# RaspFPGA.net
KiCad netlist of a schematic drawn in EAGLE
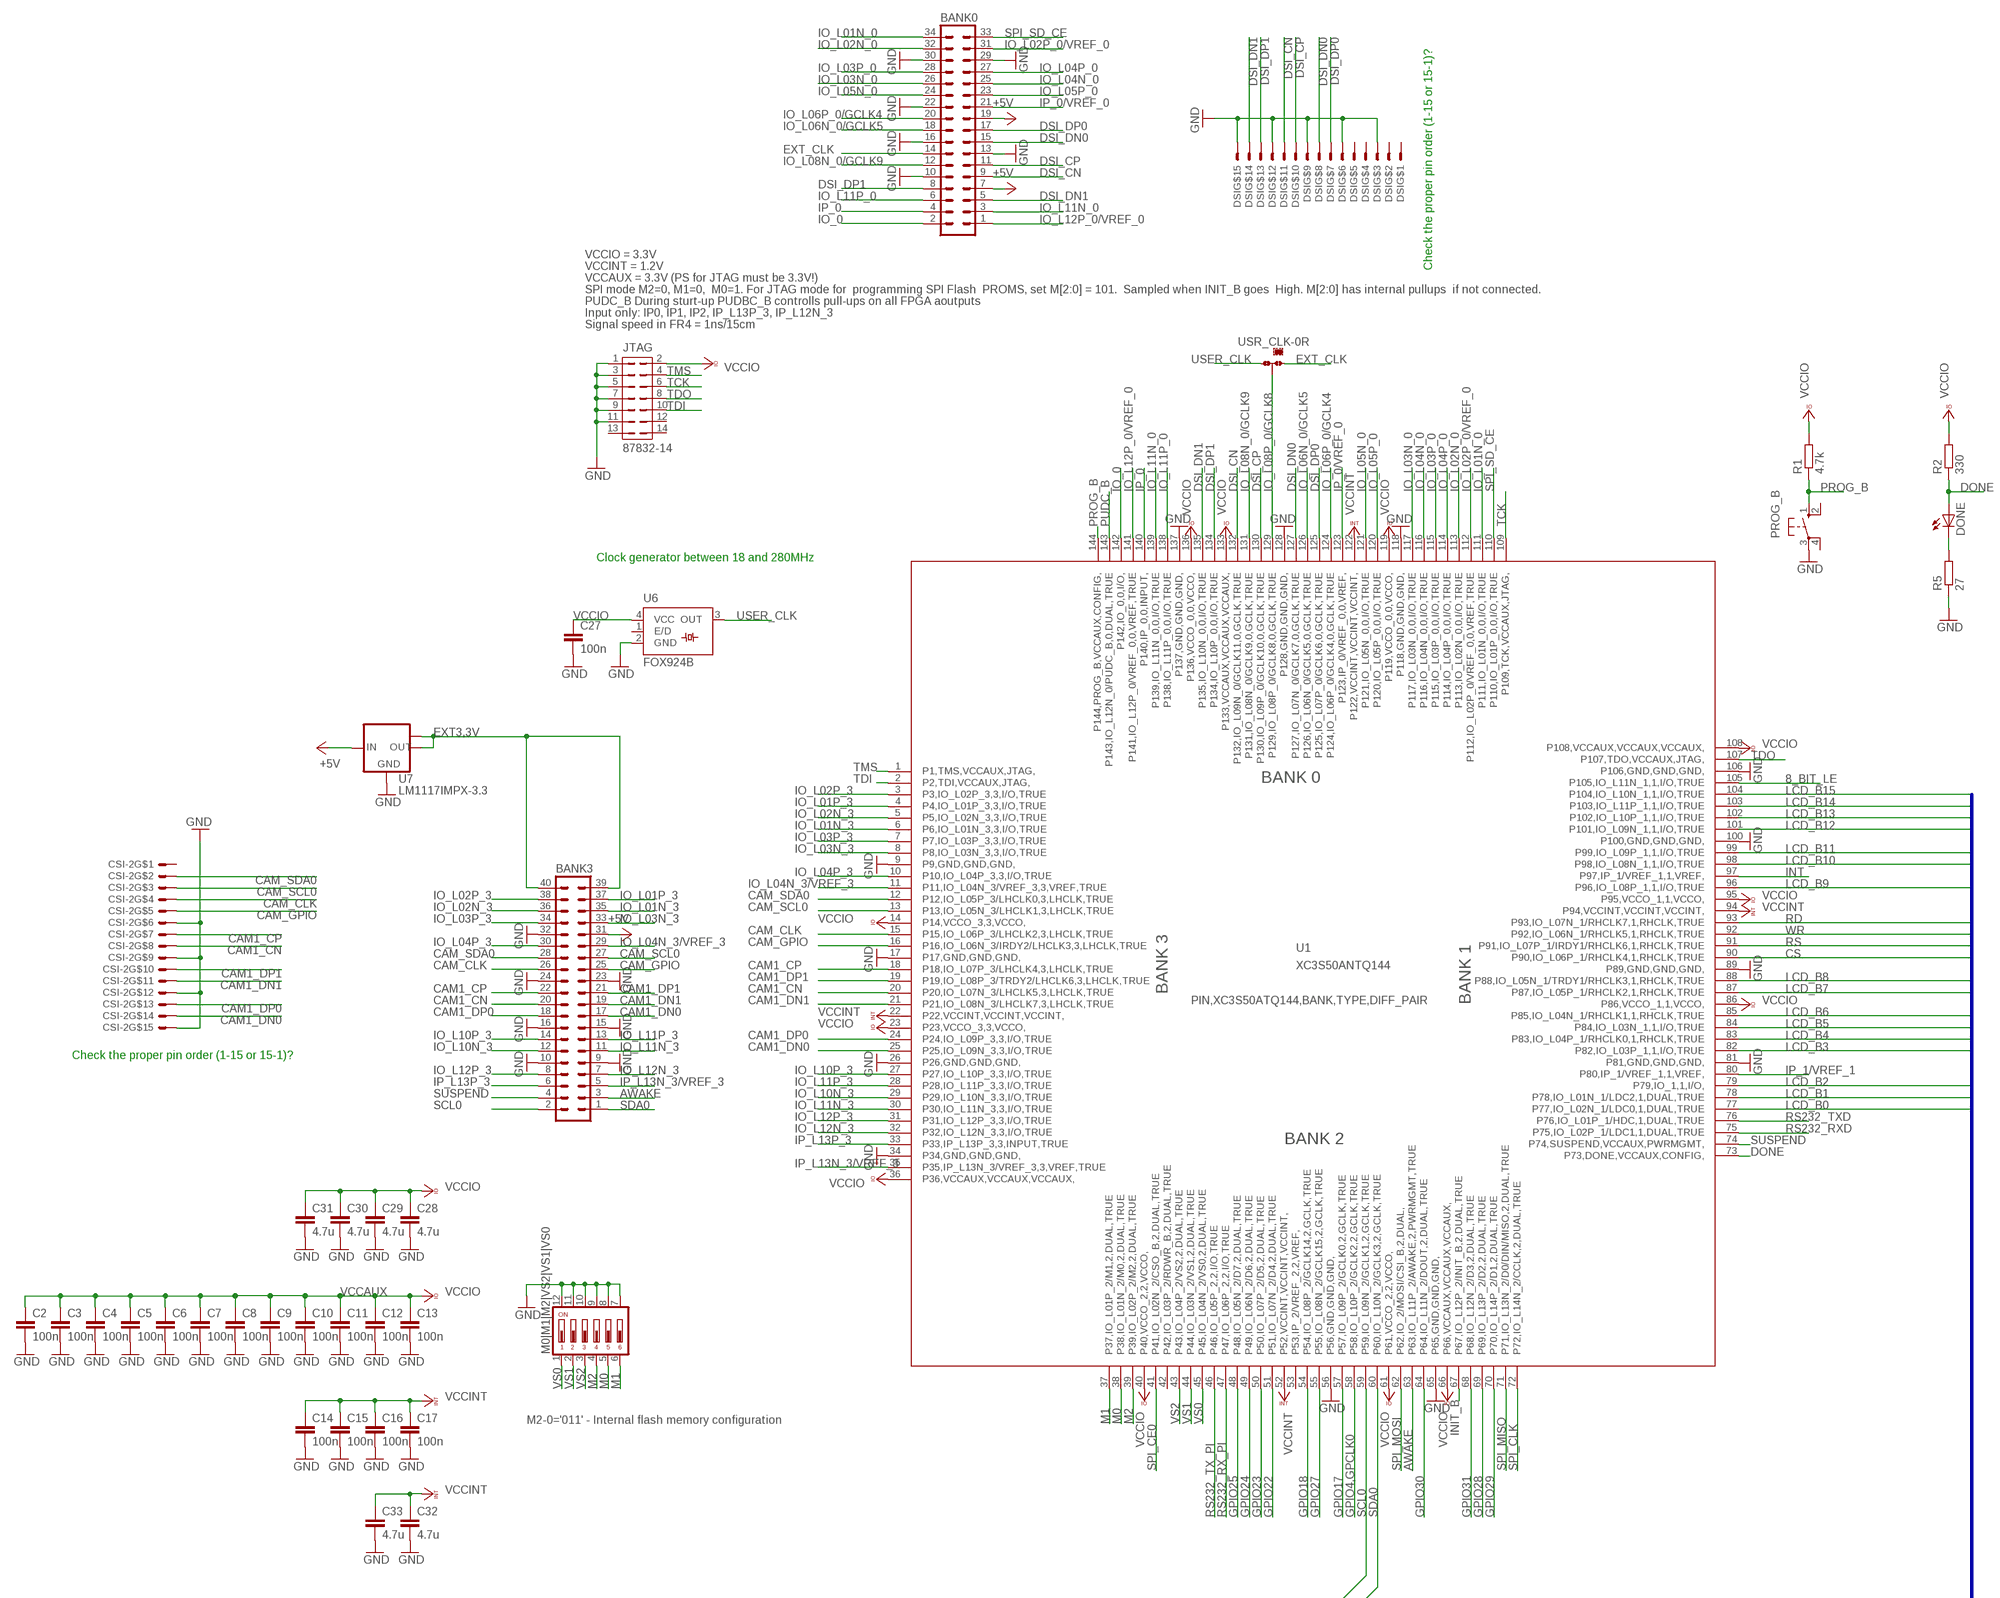
[diagram p0: schematic, sheet 1, part 1 of 3]
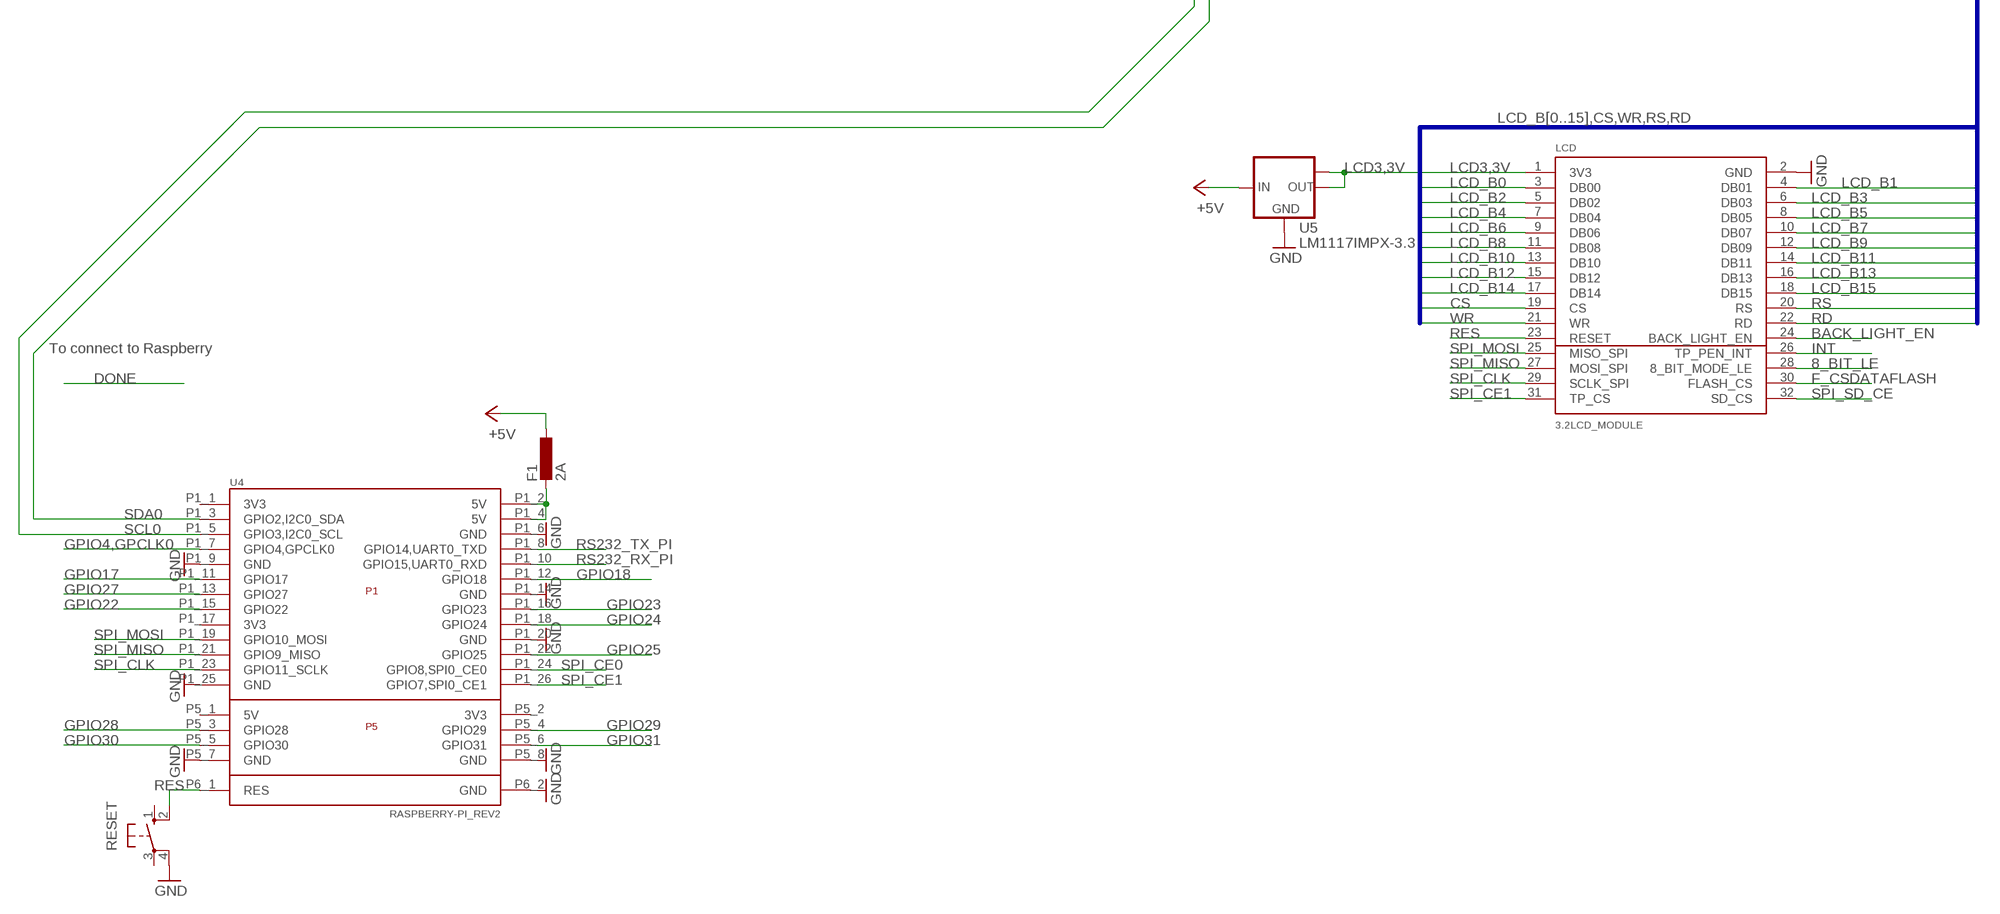
[diagram p1: schematic, sheet 1, part 2 of 3]
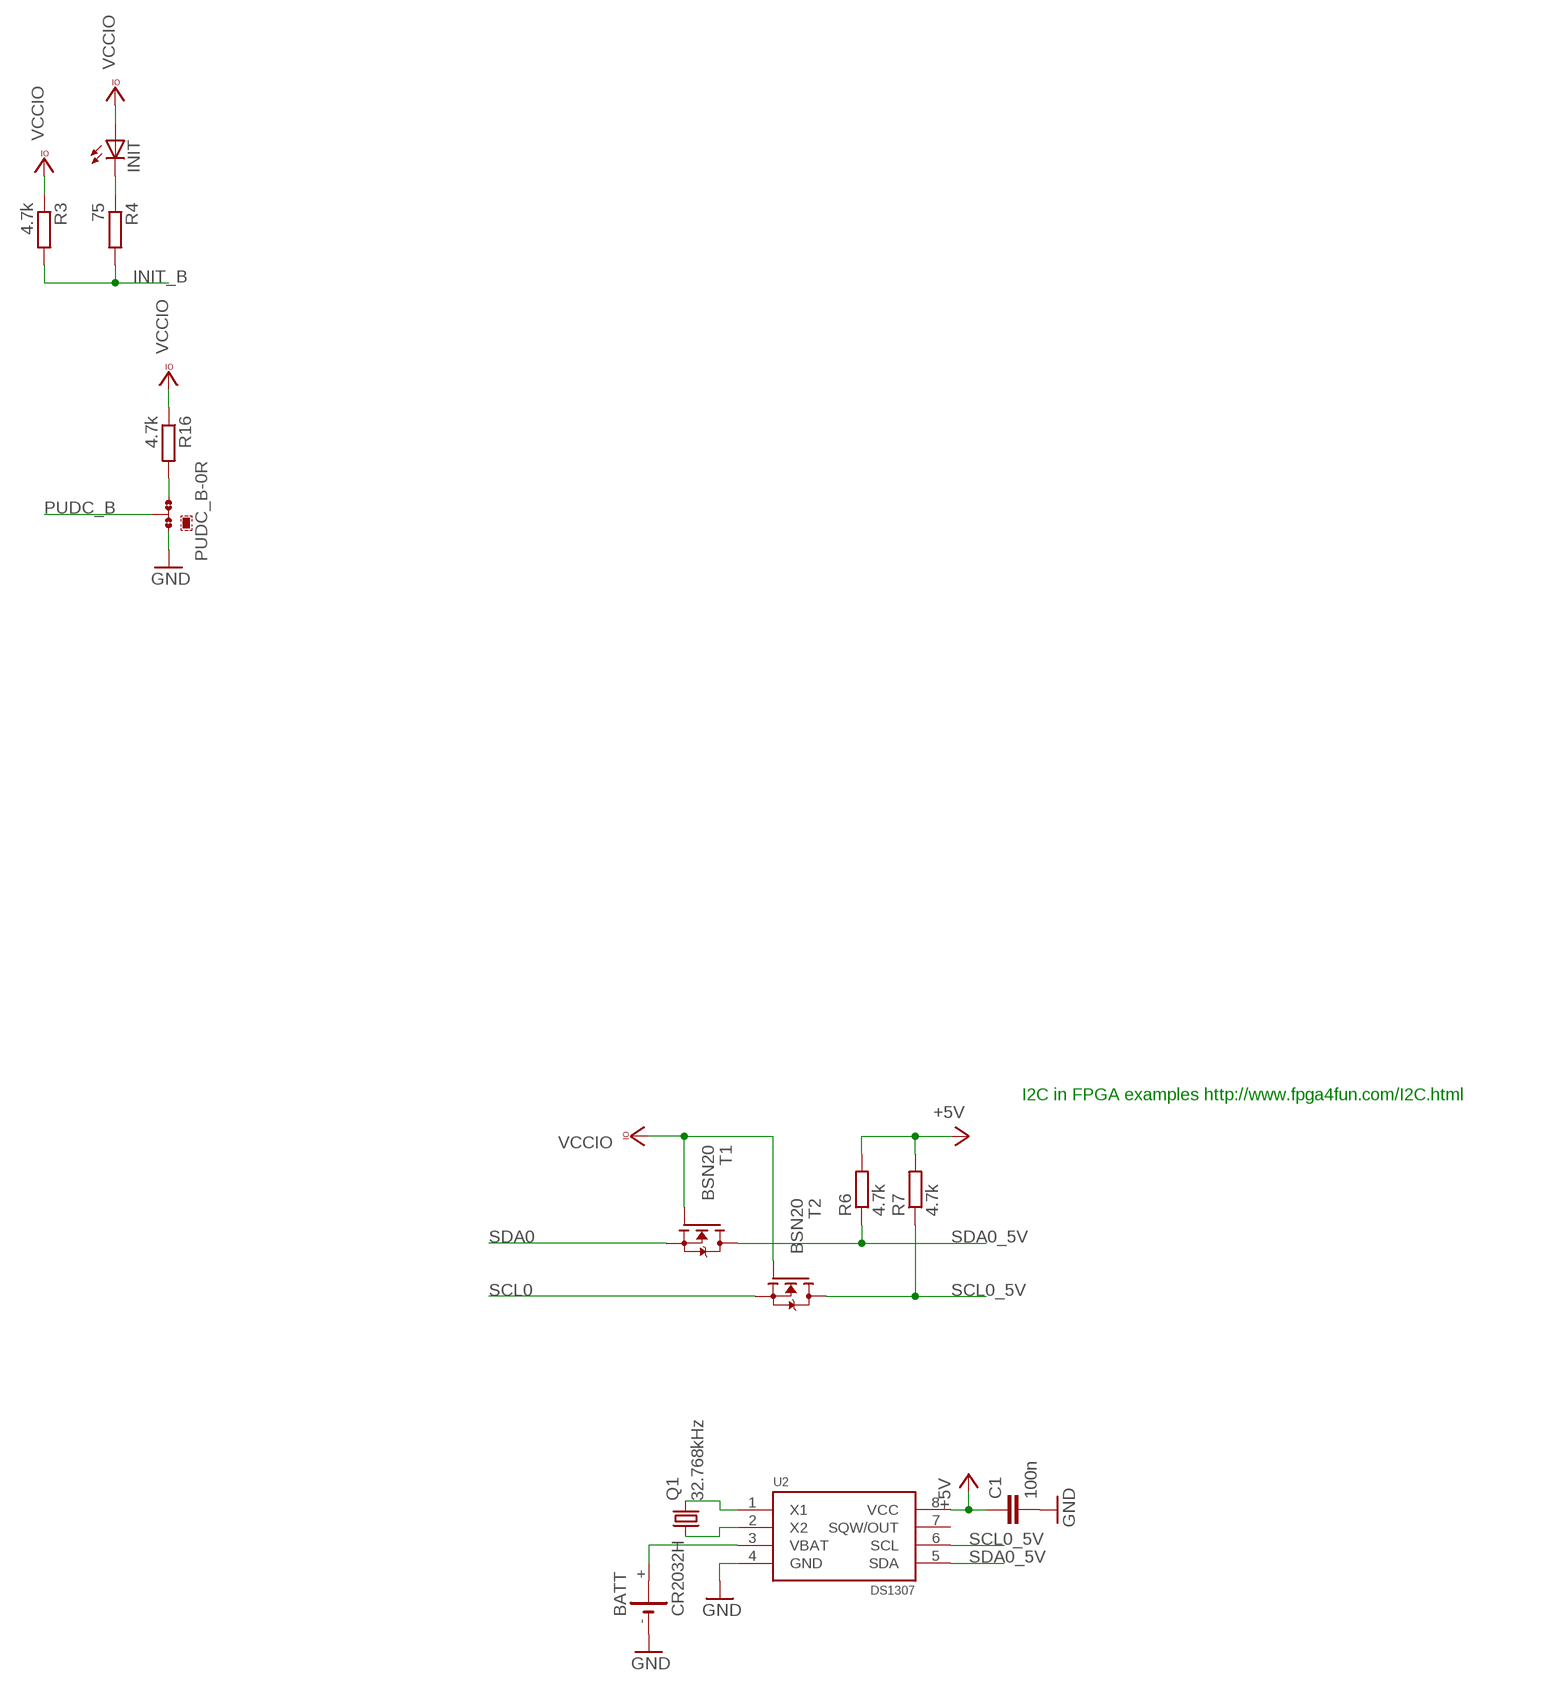
[diagram p2: schematic, sheet 1, part 3 of 3]
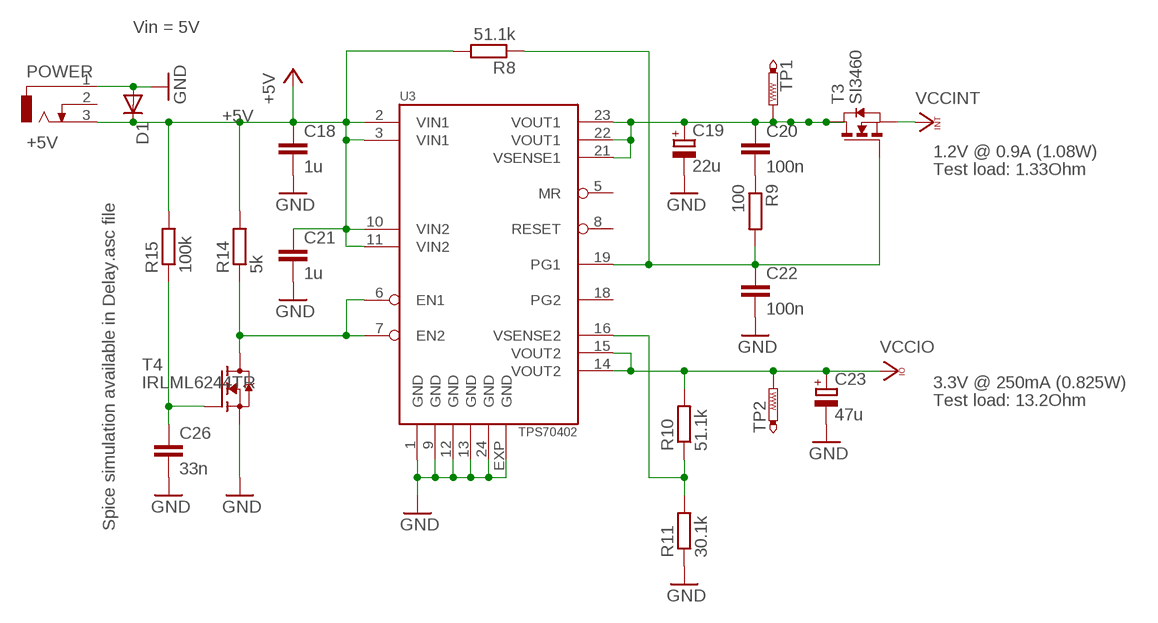
[diagram p3: schematic, sheet 2]
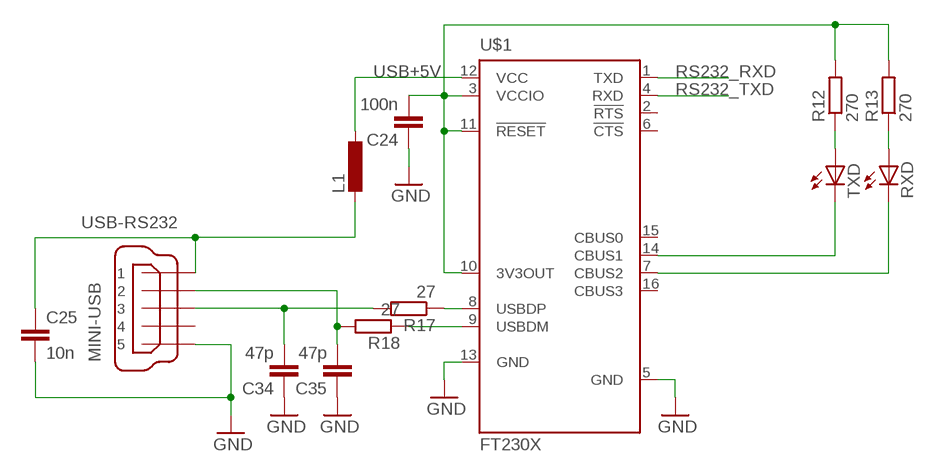
[diagram p4: schematic, sheet 3]

(export (version "E")
  (design (tool "Eeschema 10.0.6"))
  (components
    (comp (ref "C24")
      (value "100n")
      (footprint "eagle-import:C0603")
      (libsource (lib "eagle-import") (part "C-EUC0603"))
    )
    (comp (ref "C25")
      (value "10n")
      (footprint "eagle-import:C0603")
      (libsource (lib "eagle-import") (part "C-EUC0603"))
    )
    (comp (ref "C34")
      (value "47p")
      (footprint "eagle-import:C0603")
      (libsource (lib "eagle-import") (part "C-EUC0603"))
    )
    (comp (ref "C35")
      (value "47p")
      (footprint "eagle-import:C0603")
      (libsource (lib "eagle-import") (part "C-EUC0603"))
    )
    (comp (ref "L1")
      (value "L-EUL2012C")
      (footprint "eagle-import:L2012C")
      (libsource (lib "eagle-import") (part "L-EUL2012C"))
    )
    (comp (ref "R12")
      (value "270")
      (footprint "eagle-import:R0603")
      (libsource (lib "eagle-import") (part "R-EU_R0603"))
    )
    (comp (ref "R13")
      (value "270")
      (footprint "eagle-import:R0603")
      (libsource (lib "eagle-import") (part "R-EU_R0603"))
    )
    (comp (ref "R17")
      (value "27")
      (footprint "eagle-import:R0603")
      (libsource (lib "eagle-import") (part "R-EU_R0603"))
    )
    (comp (ref "R18")
      (value "27")
      (footprint "eagle-import:R0603")
      (libsource (lib "eagle-import") (part "R-EU_R0603"))
    )
    (comp (ref "RXD")
      (value "LEDCHIP-LED0805")
      (footprint "eagle-import:CHIP-LED0805")
      (libsource (lib "eagle-import") (part "LEDCHIP-LED0805"))
    )
    (comp (ref "TXD")
      (value "LEDCHIP-LED0805")
      (footprint "eagle-import:CHIP-LED0805")
      (libsource (lib "eagle-import") (part "LEDCHIP-LED0805"))
    )
    (comp (ref "U$1")
      (value "FT230X")
      (footprint "eagle-import:SSOP16")
      (libsource (lib "eagle-import") (part "FT230X"))
    )
    (comp (ref "USB-RS232")
      (value "MINI-USB")
      (footprint "eagle-import:32005-201")
      (libsource (lib "eagle-import") (part "MINI-USB-32005-201"))
    )
    (comp (ref "C18")
      (value "1u")
      (footprint "eagle-import:C1206")
      (libsource (lib "eagle-import") (part "C-EUC1206"))
    )
    (comp (ref "C19")
      (value "22u")
      (footprint "eagle-import:PANASONIC_F")
      (libsource (lib "eagle-import") (part "CPOL-EUF"))
    )
    (comp (ref "C20")
      (value "100n")
      (footprint "eagle-import:C0603")
      (libsource (lib "eagle-import") (part "C-EUC0603"))
    )
    (comp (ref "C21")
      (value "1u")
      (footprint "eagle-import:C1206")
      (libsource (lib "eagle-import") (part "C-EUC1206"))
    )
    (comp (ref "C22")
      (value "100n")
      (footprint "eagle-import:C0603")
      (libsource (lib "eagle-import") (part "C-EUC0603"))
    )
    (comp (ref "C23")
      (value "47u")
      (footprint "eagle-import:PANASONIC_F")
      (libsource (lib "eagle-import") (part "CPOL-EUF"))
    )
    (comp (ref "C26")
      (value "33n")
      (footprint "eagle-import:C0603")
      (libsource (lib "eagle-import") (part "C-EUC0603"))
    )
    (comp (ref "D1")
      (value "DIODE-DO-214AC")
      (footprint "eagle-import:DO-214AC")
      (libsource (lib "eagle-import") (part "DIODE-DO-214AC"))
    )
    (comp (ref "POWER")
      (value "+5V")
      (footprint "eagle-import:DCJ0202")
      (libsource (lib "eagle-import") (part "DCJ0202"))
    )
    (comp (ref "R8")
      (value "51.1k")
      (footprint "eagle-import:R0603")
      (libsource (lib "eagle-import") (part "R-EU_R0603"))
    )
    (comp (ref "R9")
      (value "100")
      (footprint "eagle-import:R0603")
      (libsource (lib "eagle-import") (part "R-EU_R0603"))
    )
    (comp (ref "R10")
      (value "51.1k")
      (footprint "eagle-import:R0603")
      (libsource (lib "eagle-import") (part "R-EU_R0603"))
    )
    (comp (ref "R11")
      (value "30.1k")
      (footprint "eagle-import:R0603")
      (libsource (lib "eagle-import") (part "R-EU_R0603"))
    )
    (comp (ref "R14")
      (value "5k")
      (footprint "eagle-import:R0603")
      (libsource (lib "eagle-import") (part "R-EU_R0603"))
    )
    (comp (ref "R15")
      (value "100k")
      (footprint "eagle-import:R0603")
      (libsource (lib "eagle-import") (part "R-EU_R0603"))
    )
    (comp (ref "T3")
      (value "SI3460")
      (footprint "eagle-import:SOT23-6")
      (libsource (lib "eagle-import") (part "SI3460"))
    )
    (comp (ref "T4")
      (value "IRLML6244TR")
      (footprint "eagle-import:SOT23")
      (libsource (lib "eagle-import") (part "IRLML6244TR"))
    )
    (comp (ref "TP1")
      (value "PTR1B1,27")
      (footprint "eagle-import:B1,27")
      (libsource (lib "eagle-import") (part "PTR1B1,27"))
    )
    (comp (ref "TP2")
      (value "PTR1B1,27")
      (footprint "eagle-import:B1,27")
      (libsource (lib "eagle-import") (part "PTR1B1,27"))
    )
    (comp (ref "U3")
      (value "TPS70402")
      (footprint "eagle-import:HTSSOP24PWP")
      (libsource (lib "eagle-import") (part "TPS70402"))
    )
    (comp (ref "BANK0")
      (value "MA17-2W")
      (footprint "eagle-import:MA17-2W")
      (libsource (lib "eagle-import") (part "MA17-2W"))
    )
    (comp (ref "BANK3")
      (value "MA20-2W")
      (footprint "eagle-import:MA20-2W")
      (libsource (lib "eagle-import") (part "MA20-2W"))
    )
    (comp (ref "BATT")
      (value "CR2032H")
      (footprint "eagle-import:CR2032H")
      (libsource (lib "eagle-import") (part "CR2032H"))
    )
    (comp (ref "C1")
      (value "100n")
      (footprint "eagle-import:C0603")
      (libsource (lib "eagle-import") (part "C-EUC0603"))
    )
    (comp (ref "C2")
      (value "100n")
      (footprint "eagle-import:C0603")
      (libsource (lib "eagle-import") (part "C-EUC0603"))
    )
    (comp (ref "C3")
      (value "100n")
      (footprint "eagle-import:C0603")
      (libsource (lib "eagle-import") (part "C-EUC0603"))
    )
    (comp (ref "C4")
      (value "100n")
      (footprint "eagle-import:C0603")
      (libsource (lib "eagle-import") (part "C-EUC0603"))
    )
    (comp (ref "C5")
      (value "100n")
      (footprint "eagle-import:C0603")
      (libsource (lib "eagle-import") (part "C-EUC0603"))
    )
    (comp (ref "C6")
      (value "100n")
      (footprint "eagle-import:C0603")
      (libsource (lib "eagle-import") (part "C-EUC0603"))
    )
    (comp (ref "C7")
      (value "100n")
      (footprint "eagle-import:C0603")
      (libsource (lib "eagle-import") (part "C-EUC0603"))
    )
    (comp (ref "C8")
      (value "100n")
      (footprint "eagle-import:C0603")
      (libsource (lib "eagle-import") (part "C-EUC0603"))
    )
    (comp (ref "C9")
      (value "100n")
      (footprint "eagle-import:C0603")
      (libsource (lib "eagle-import") (part "C-EUC0603"))
    )
    (comp (ref "C10")
      (value "100n")
      (footprint "eagle-import:C0603")
      (libsource (lib "eagle-import") (part "C-EUC0603"))
    )
    (comp (ref "C11")
      (value "100n")
      (footprint "eagle-import:C0603")
      (libsource (lib "eagle-import") (part "C-EUC0603"))
    )
    (comp (ref "C12")
      (value "100n")
      (footprint "eagle-import:C0603")
      (libsource (lib "eagle-import") (part "C-EUC0603"))
    )
    (comp (ref "C13")
      (value "100n")
      (footprint "eagle-import:C0603")
      (libsource (lib "eagle-import") (part "C-EUC0603"))
    )
    (comp (ref "C14")
      (value "100n")
      (footprint "eagle-import:C0603")
      (libsource (lib "eagle-import") (part "C-EUC0603"))
    )
    (comp (ref "C15")
      (value "100n")
      (footprint "eagle-import:C0603")
      (libsource (lib "eagle-import") (part "C-EUC0603"))
    )
    (comp (ref "C16")
      (value "100n")
      (footprint "eagle-import:C0603")
      (libsource (lib "eagle-import") (part "C-EUC0603"))
    )
    (comp (ref "C17")
      (value "100n")
      (footprint "eagle-import:C0603")
      (libsource (lib "eagle-import") (part "C-EUC0603"))
    )
    (comp (ref "C27")
      (value "100n")
      (footprint "eagle-import:C0603")
      (libsource (lib "eagle-import") (part "C-EUC0603"))
    )
    (comp (ref "C28")
      (value "4.7u")
      (footprint "eagle-import:C0603")
      (libsource (lib "eagle-import") (part "C-EUC0603"))
    )
    (comp (ref "C29")
      (value "4.7u")
      (footprint "eagle-import:C0603")
      (libsource (lib "eagle-import") (part "C-EUC0603"))
    )
    (comp (ref "C30")
      (value "4.7u")
      (footprint "eagle-import:C0603")
      (libsource (lib "eagle-import") (part "C-EUC0603"))
    )
    (comp (ref "C31")
      (value "4.7u")
      (footprint "eagle-import:C0603")
      (libsource (lib "eagle-import") (part "C-EUC0603"))
    )
    (comp (ref "C32")
      (value "4.7u")
      (footprint "eagle-import:C0603")
      (libsource (lib "eagle-import") (part "C-EUC0603"))
    )
    (comp (ref "C33")
      (value "4.7u")
      (footprint "eagle-import:C0603")
      (libsource (lib "eagle-import") (part "C-EUC0603"))
    )
    (comp (ref "CSI-2")
      (value "52271-1579")
      (footprint "eagle-import:52271-1579")
      (libsource (lib "eagle-import") (part "52271-1579"))
    )
    (comp (ref "DONE")
      (value "LEDCHIP-LED0603")
      (footprint "eagle-import:CHIP-LED0603")
      (libsource (lib "eagle-import") (part "LEDCHIP-LED0603"))
    )
    (comp (ref "DSI")
      (value "52271-1579")
      (footprint "eagle-import:52271-1579")
      (libsource (lib "eagle-import") (part "52271-1579"))
    )
    (comp (ref "F1")
      (value "2A")
      (footprint "eagle-import:L1812")
      (libsource (lib "eagle-import") (part "L-EUL1812"))
    )
    (comp (ref "INIT")
      (value "LEDCHIP-LED0603")
      (footprint "eagle-import:CHIP-LED0603")
      (libsource (lib "eagle-import") (part "LEDCHIP-LED0603"))
    )
    (comp (ref "JTAG")
      (value "87832-14")
      (footprint "eagle-import:87832-14")
      (libsource (lib "eagle-import") (part "87832-14"))
    )
    (comp (ref "LCD")
      (value "3.2LCD_MODULE")
      (footprint "eagle-import:3.2LCD_MODULE")
      (libsource (lib "eagle-import") (part "3.2LCD_MODULE"))
    )
    (comp (ref "M0|M1|M2|VS2|VS1|VS0")
      (value "DIP06YL")
      (footprint "eagle-import:DIP06YL")
      (libsource (lib "eagle-import") (part "DIP06YL"))
    )
    (comp (ref "PROG_B")
      (value "10-XX")
      (footprint "eagle-import:B3F-10XX")
      (libsource (lib "eagle-import") (part "10-XX"))
    )
    (comp (ref "PUDC_B")
      (value "0R-JUMPA")
      (footprint "eagle-import:A0R-JMP")
      (libsource (lib "eagle-import") (part "0R-JUMPA"))
    )
    (comp (ref "Q1")
      (value "32.768kHz")
      (footprint "eagle-import:TC38H")
      (libsource (lib "eagle-import") (part "CRYSTALTC38H"))
    )
    (comp (ref "R1")
      (value "4.7k")
      (footprint "eagle-import:R0603")
      (libsource (lib "eagle-import") (part "R-EU_R0603"))
    )
    (comp (ref "R2")
      (value "330")
      (footprint "eagle-import:R0603")
      (libsource (lib "eagle-import") (part "R-EU_R0603"))
    )
    (comp (ref "R3")
      (value "4.7k")
      (footprint "eagle-import:R0603")
      (libsource (lib "eagle-import") (part "R-EU_R0603"))
    )
    (comp (ref "R4")
      (value "75")
      (footprint "eagle-import:R0603")
      (libsource (lib "eagle-import") (part "R-EU_R0603"))
    )
    (comp (ref "R5")
      (value "27")
      (footprint "eagle-import:R0603")
      (libsource (lib "eagle-import") (part "R-EU_R0603"))
    )
    (comp (ref "R6")
      (value "4.7k")
      (footprint "eagle-import:R0603")
      (libsource (lib "eagle-import") (part "R-EU_R0603"))
    )
    (comp (ref "R7")
      (value "4.7k")
      (footprint "eagle-import:R0603")
      (libsource (lib "eagle-import") (part "R-EU_R0603"))
    )
    (comp (ref "R16")
      (value "4.7k")
      (footprint "eagle-import:R0603")
      (libsource (lib "eagle-import") (part "R-EU_R0603"))
    )
    (comp (ref "RESET")
      (value "10-XX")
      (footprint "eagle-import:B3F-10XX")
      (libsource (lib "eagle-import") (part "10-XX"))
    )
    (comp (ref "T1")
      (value "BSN20")
      (footprint "eagle-import:SOT23")
      (libsource (lib "eagle-import") (part "BSN20"))
    )
    (comp (ref "T2")
      (value "BSN20")
      (footprint "eagle-import:SOT23")
      (libsource (lib "eagle-import") (part "BSN20"))
    )
    (comp (ref "U1")
      (value "XC3S50ANTQ144")
      (footprint "eagle-import:TQ144")
      (libsource (lib "eagle-import") (part "XC3S50ANTQ144"))
    )
    (comp (ref "U2")
      (value "DS1307")
      (footprint "eagle-import:SO8")
      (libsource (lib "eagle-import") (part "DS1307"))
    )
    (comp (ref "U4")
      (value "RASPBERRY-PI_REV2")
      (footprint "eagle-import:RASPBERRY-PI_REV2")
      (libsource (lib "eagle-import") (part "RASPBERRY-PI_REV2"))
    )
    (comp (ref "U5")
      (value "LM1117IMPX-3.3")
      (footprint "eagle-import:SOT223")
      (libsource (lib "eagle-import") (part "LM1117IMPX-3.3"))
    )
    (comp (ref "U6")
      (value "FOX924B")
      (footprint "eagle-import:FOX924B")
      (libsource (lib "eagle-import") (part "FOX924B"))
    )
    (comp (ref "U7")
      (value "LM1117IMPX-3.3")
      (footprint "eagle-import:SOT223")
      (libsource (lib "eagle-import") (part "LM1117IMPX-3.3"))
    )
    (comp (ref "USR_CLK")
      (value "0R-JUMPA")
      (footprint "eagle-import:A0R-JMP")
      (libsource (lib "eagle-import") (part "0R-JUMPA"))
    )
  )
  (nets
    (net (code "1") (name "+5V") (class "Default")
      (node (ref "BANK0") (pin "19") (pinfunction "19_19") (pintype "passive"))
      (node (ref "BANK0") (pin "7") (pinfunction "7_7") (pintype "passive"))
      (node (ref "BANK3") (pin "31") (pinfunction "31_31") (pintype "passive"))
      (node (ref "C1") (pin "1") (pinfunction "1_1") (pintype "passive"))
      (node (ref "C18") (pin "1") (pinfunction "1_1") (pintype "passive"))
      (node (ref "C21") (pin "1") (pinfunction "1_1") (pintype "passive"))
      (node (ref "D1") (pin "C") (pinfunction "C_C") (pintype "passive"))
      (node (ref "F1") (pin "1") (pinfunction "1_1") (pintype "passive"))
      (node (ref "POWER") (pin "3") (pinfunction "3_3") (pintype "passive"))
      (node (ref "R14") (pin "2") (pinfunction "2_2") (pintype "passive"))
      (node (ref "R15") (pin "2") (pinfunction "2_2") (pintype "passive"))
      (node (ref "R6") (pin "2") (pinfunction "2_2") (pintype "passive"))
      (node (ref "R7") (pin "2") (pinfunction "2_2") (pintype "passive"))
      (node (ref "R8") (pin "2") (pinfunction "2_2") (pintype "passive"))
      (node (ref "U2") (pin "8") (pinfunction "VCC_8") (pintype "bidirectional"))
      (node (ref "U3") (pin "10") (pinfunction "VIN2_10") (pintype "bidirectional"))
      (node (ref "U3") (pin "11") (pinfunction "VIN2_11") (pintype "bidirectional"))
      (node (ref "U3") (pin "2") (pinfunction "VIN1_2") (pintype "bidirectional"))
      (node (ref "U3") (pin "3") (pinfunction "VIN1_3") (pintype "bidirectional"))
      (node (ref "U5") (pin "3") (pinfunction "IN_3") (pintype "input"))
      (node (ref "U7") (pin "3") (pinfunction "IN_3") (pintype "input"))
    )
    (net (code "3") (name "8_BIT_LE") (class "Default")
      (node (ref "LCD") (pin "28") (pinfunction "8_BIT_MODE_LE_28") (pintype "bidirectional"))
      (node (ref "U1") (pin "105") (pinfunction "P105,IO_L11N_1,1,I/O,TRUE_105") (pintype "passive"))
    )
    (net (code "4") (name "AWAKE") (class "Default")
      (node (ref "BANK3") (pin "3") (pinfunction "3_3") (pintype "passive"))
      (node (ref "U1") (pin "63") (pinfunction "P63,IO_L11P_2/AWAKE,2,PWRMGMT,TRUE_63") (pintype "passive"))
    )
    (net (code "5") (name "BACK_LIGHT_EN") (class "Default")
      (node (ref "LCD") (pin "24") (pinfunction "BACK_LIGHT_EN_24") (pintype "bidirectional"))
    )
    (net (code "6") (name "CAM1_CN") (class "Default")
      (node (ref "BANK3") (pin "20") (pinfunction "20_20") (pintype "passive"))
      (node (ref "CSI-2") (pin "P$8") (pinfunction "S_P$8") (pintype "passive"))
      (node (ref "U1") (pin "20") (pinfunction "P20,IO_L07N_3/LHCLK5,3,LHCLK,TRUE_20") (pintype "passive"))
    )
    (net (code "7") (name "CAM1_CP") (class "Default")
      (node (ref "BANK3") (pin "22") (pinfunction "22_22") (pintype "passive"))
      (node (ref "CSI-2") (pin "P$7") (pinfunction "S_P$7") (pintype "passive"))
      (node (ref "U1") (pin "18") (pinfunction "P18,IO_L07P_3/LHCLK4,3,LHCLK,TRUE_18") (pintype "passive"))
    )
    (net (code "8") (name "CAM1_DN0") (class "Default")
      (node (ref "BANK3") (pin "17") (pinfunction "17_17") (pintype "passive"))
      (node (ref "CSI-2") (pin "P$14") (pinfunction "S_P$14") (pintype "passive"))
      (node (ref "U1") (pin "25") (pinfunction "P25,IO_L09N_3,3,I/O,TRUE_25") (pintype "passive"))
    )
    (net (code "9") (name "CAM1_DN1") (class "Default")
      (node (ref "BANK3") (pin "19") (pinfunction "19_19") (pintype "passive"))
      (node (ref "CSI-2") (pin "P$11") (pinfunction "S_P$11") (pintype "passive"))
      (node (ref "U1") (pin "21") (pinfunction "P21,IO_L08N_3/LHCLK7,3,LHCLK,TRUE_21") (pintype "passive"))
    )
    (net (code "10") (name "CAM1_DP0") (class "Default")
      (node (ref "BANK3") (pin "18") (pinfunction "18_18") (pintype "passive"))
      (node (ref "CSI-2") (pin "P$13") (pinfunction "S_P$13") (pintype "passive"))
      (node (ref "U1") (pin "24") (pinfunction "P24,IO_L09P_3,3,I/O,TRUE_24") (pintype "passive"))
    )
    (net (code "11") (name "CAM1_DP1") (class "Default")
      (node (ref "BANK3") (pin "21") (pinfunction "21_21") (pintype "passive"))
      (node (ref "CSI-2") (pin "P$10") (pinfunction "S_P$10") (pintype "passive"))
      (node (ref "U1") (pin "19") (pinfunction "P19,IO_L08P_3/TRDY2/LHCLK6,3,LHCLK,TRUE_19") (pintype "passive"))
    )
    (net (code "12") (name "CAM_CLK") (class "Default")
      (node (ref "BANK3") (pin "26") (pinfunction "26_26") (pintype "passive"))
      (node (ref "CSI-2") (pin "P$4") (pinfunction "S_P$4") (pintype "passive"))
      (node (ref "U1") (pin "15") (pinfunction "P15,IO_L06P_3/LHCLK2,3,LHCLK,TRUE_15") (pintype "passive"))
    )
    (net (code "13") (name "CAM_GPIO") (class "Default")
      (node (ref "BANK3") (pin "25") (pinfunction "25_25") (pintype "passive"))
      (node (ref "CSI-2") (pin "P$5") (pinfunction "S_P$5") (pintype "passive"))
      (node (ref "U1") (pin "16") (pinfunction "P16,IO_L06N_3/IRDY2/LHCLK3,3,LHCLK,TRUE_16") (pintype "passive"))
    )
    (net (code "14") (name "CAM_SCL0") (class "Default")
      (node (ref "BANK3") (pin "27") (pinfunction "27_27") (pintype "passive"))
      (node (ref "CSI-2") (pin "P$3") (pinfunction "S_P$3") (pintype "passive"))
      (node (ref "U1") (pin "13") (pinfunction "P13,IO_L05N_3/LHCLK1,3,LHCLK,TRUE_13") (pintype "passive"))
    )
    (net (code "15") (name "CAM_SDA0") (class "Default")
      (node (ref "BANK3") (pin "28") (pinfunction "28_28") (pintype "passive"))
      (node (ref "CSI-2") (pin "P$2") (pinfunction "S_P$2") (pintype "passive"))
      (node (ref "U1") (pin "12") (pinfunction "P12,IO_L05P_3/LHCLK0,3,LHCLK,TRUE_12") (pintype "passive"))
    )
    (net (code "16") (name "CS") (class "Default")
      (node (ref "LCD") (pin "19") (pinfunction "CS_19") (pintype "bidirectional"))
      (node (ref "U1") (pin "90") (pinfunction "P90,IO_L06P_1/RHCLK4,1,RHCLK,TRUE_90") (pintype "passive"))
    )
    (net (code "17") (name "DONE") (class "Default")
      (node (ref "DONE") (pin "A") (pinfunction "A_A") (pintype "passive"))
      (node (ref "R2") (pin "1") (pinfunction "1_1") (pintype "passive"))
      (node (ref "U1") (pin "73") (pinfunction "P73,DONE,VCCAUX,CONFIG,_73") (pintype "passive"))
    )
    (net (code "18") (name "DSI_CN") (class "Default")
      (node (ref "BANK0") (pin "9") (pinfunction "9_9") (pintype "passive"))
      (node (ref "DSI") (pin "P$11") (pinfunction "S_P$11") (pintype "passive"))
      (node (ref "U1") (pin "132") (pinfunction "P132,IO_L09N_0/GCLK11,0,GCLK,TRUE_132") (pintype "passive"))
    )
    (net (code "19") (name "DSI_CP") (class "Default")
      (node (ref "BANK0") (pin "11") (pinfunction "11_11") (pintype "passive"))
      (node (ref "DSI") (pin "P$10") (pinfunction "S_P$10") (pintype "passive"))
      (node (ref "U1") (pin "130") (pinfunction "P130,IO_L09P_0/GCLK10,0,GCLK,TRUE_130") (pintype "passive"))
    )
    (net (code "20") (name "DSI_DN0") (class "Default")
      (node (ref "BANK0") (pin "15") (pinfunction "15_15") (pintype "passive"))
      (node (ref "DSI") (pin "P$8") (pinfunction "S_P$8") (pintype "passive"))
      (node (ref "U1") (pin "127") (pinfunction "P127,IO_L07N_0/GCLK7,0,GCLK,TRUE_127") (pintype "passive"))
    )
    (net (code "21") (name "DSI_DN1") (class "Default")
      (node (ref "BANK0") (pin "5") (pinfunction "5_5") (pintype "passive"))
      (node (ref "DSI") (pin "P$14") (pinfunction "S_P$14") (pintype "passive"))
      (node (ref "U1") (pin "135") (pinfunction "P135,IO_L10N_0,0,I/O,TRUE_135") (pintype "passive"))
    )
    (net (code "22") (name "DSI_DP0") (class "Default")
      (node (ref "BANK0") (pin "17") (pinfunction "17_17") (pintype "passive"))
      (node (ref "DSI") (pin "P$7") (pinfunction "S_P$7") (pintype "passive"))
      (node (ref "U1") (pin "125") (pinfunction "P125,IO_L07P_0/GCLK6,0,GCLK,TRUE_125") (pintype "passive"))
    )
    (net (code "23") (name "DSI_DP1") (class "Default")
      (node (ref "BANK0") (pin "8") (pinfunction "8_8") (pintype "passive"))
      (node (ref "DSI") (pin "P$13") (pinfunction "S_P$13") (pintype "passive"))
      (node (ref "U1") (pin "134") (pinfunction "P134,IO_L10P_0,0,I/O,TRUE_134") (pintype "passive"))
    )
    (net (code "24") (name "EXT3,3V") (class "Default")
      (node (ref "BANK3") (pin "39") (pinfunction "39_39") (pintype "passive"))
      (node (ref "BANK3") (pin "40") (pinfunction "40_40") (pintype "passive"))
      (node (ref "U7") (pin "2") (pinfunction "OUT_2") (pintype "passive"))
      (node (ref "U7") (pin "TAB") (pinfunction "OUT1_TAB") (pintype "passive"))
    )
    (net (code "25") (name "EXT_CLK") (class "Default")
      (node (ref "BANK0") (pin "14") (pinfunction "14_14") (pintype "passive"))
      (node (ref "USR_CLK") (pin "1") (pinfunction "1_1") (pintype "passive"))
    )
    (net (code "26") (name "F_CSDATAFLASH") (class "Default")
      (node (ref "LCD") (pin "30") (pinfunction "FLASH_CS_30") (pintype "bidirectional"))
    )
    (net (code "27") (name "GND") (class "Default")
      (node (ref "BANK0") (pin "10") (pinfunction "10_10") (pintype "passive"))
      (node (ref "BANK0") (pin "13") (pinfunction "13_13") (pintype "passive"))
      (node (ref "BANK0") (pin "16") (pinfunction "16_16") (pintype "passive"))
      (node (ref "BANK0") (pin "22") (pinfunction "22_22") (pintype "passive"))
      (node (ref "BANK0") (pin "29") (pinfunction "29_29") (pintype "passive"))
      (node (ref "BANK0") (pin "30") (pinfunction "30_30") (pintype "passive"))
      (node (ref "BANK3") (pin "10") (pinfunction "10_10") (pintype "passive"))
      (node (ref "BANK3") (pin "15") (pinfunction "15_15") (pintype "passive"))
      (node (ref "BANK3") (pin "16") (pinfunction "16_16") (pintype "passive"))
      (node (ref "BANK3") (pin "23") (pinfunction "23_23") (pintype "passive"))
      (node (ref "BANK3") (pin "24") (pinfunction "24_24") (pintype "passive"))
      (node (ref "BANK3") (pin "32") (pinfunction "32_32") (pintype "passive"))
      (node (ref "BANK3") (pin "9") (pinfunction "9_9") (pintype "passive"))
      (node (ref "BATT") (pin "-") (pinfunction "-_-") (pintype "passive"))
      (node (ref "C1") (pin "2") (pinfunction "2_2") (pintype "passive"))
      (node (ref "C10") (pin "2") (pinfunction "2_2") (pintype "passive"))
      (node (ref "C11") (pin "2") (pinfunction "2_2") (pintype "passive"))
      (node (ref "C12") (pin "2") (pinfunction "2_2") (pintype "passive"))
      (node (ref "C13") (pin "2") (pinfunction "2_2") (pintype "passive"))
      (node (ref "C14") (pin "2") (pinfunction "2_2") (pintype "passive"))
      (node (ref "C15") (pin "2") (pinfunction "2_2") (pintype "passive"))
      (node (ref "C16") (pin "2") (pinfunction "2_2") (pintype "passive"))
      (node (ref "C17") (pin "2") (pinfunction "2_2") (pintype "passive"))
      (node (ref "C18") (pin "2") (pinfunction "2_2") (pintype "passive"))
      (node (ref "C19") (pin "-") (pinfunction "-_-") (pintype "passive"))
      (node (ref "C2") (pin "2") (pinfunction "2_2") (pintype "passive"))
      (node (ref "C21") (pin "2") (pinfunction "2_2") (pintype "passive"))
      (node (ref "C22") (pin "2") (pinfunction "2_2") (pintype "passive"))
      (node (ref "C23") (pin "-") (pinfunction "-_-") (pintype "passive"))
      (node (ref "C24") (pin "1") (pinfunction "1_1") (pintype "passive"))
      (node (ref "C25") (pin "2") (pinfunction "2_2") (pintype "passive"))
      (node (ref "C26") (pin "2") (pinfunction "2_2") (pintype "passive"))
      (node (ref "C27") (pin "2") (pinfunction "2_2") (pintype "passive"))
      (node (ref "C28") (pin "2") (pinfunction "2_2") (pintype "passive"))
      (node (ref "C29") (pin "2") (pinfunction "2_2") (pintype "passive"))
      (node (ref "C3") (pin "2") (pinfunction "2_2") (pintype "passive"))
      (node (ref "C30") (pin "2") (pinfunction "2_2") (pintype "passive"))
      (node (ref "C31") (pin "2") (pinfunction "2_2") (pintype "passive"))
      (node (ref "C32") (pin "2") (pinfunction "2_2") (pintype "passive"))
      (node (ref "C33") (pin "2") (pinfunction "2_2") (pintype "passive"))
      (node (ref "C34") (pin "1") (pinfunction "1_1") (pintype "passive"))
      (node (ref "C35") (pin "1") (pinfunction "1_1") (pintype "passive"))
      (node (ref "C4") (pin "2") (pinfunction "2_2") (pintype "passive"))
      (node (ref "C5") (pin "2") (pinfunction "2_2") (pintype "passive"))
      (node (ref "C6") (pin "2") (pinfunction "2_2") (pintype "passive"))
      (node (ref "C7") (pin "2") (pinfunction "2_2") (pintype "passive"))
      (node (ref "C8") (pin "2") (pinfunction "2_2") (pintype "passive"))
      (node (ref "C9") (pin "2") (pinfunction "2_2") (pintype "passive"))
      (node (ref "CSI-2") (pin "P$12") (pinfunction "S_P$12") (pintype "passive"))
      (node (ref "CSI-2") (pin "P$15") (pinfunction "S_P$15") (pintype "passive"))
      (node (ref "CSI-2") (pin "P$6") (pinfunction "S_P$6") (pintype "passive"))
      (node (ref "CSI-2") (pin "P$9") (pinfunction "S_P$9") (pintype "passive"))
      (node (ref "D1") (pin "A") (pinfunction "A_A") (pintype "passive"))
      (node (ref "DSI") (pin "P$12") (pinfunction "S_P$12") (pintype "passive"))
      (node (ref "DSI") (pin "P$15") (pinfunction "S_P$15") (pintype "passive"))
      (node (ref "DSI") (pin "P$3") (pinfunction "S_P$3") (pintype "passive"))
      (node (ref "DSI") (pin "P$6") (pinfunction "S_P$6") (pintype "passive"))
      (node (ref "DSI") (pin "P$9") (pinfunction "S_P$9") (pintype "passive"))
      (node (ref "JTAG") (pin "1") (pinfunction "1_1") (pintype "passive"))
      (node (ref "JTAG") (pin "11") (pinfunction "11_11") (pintype "passive"))
      (node (ref "JTAG") (pin "3") (pinfunction "3_3") (pintype "passive"))
      (node (ref "JTAG") (pin "5") (pinfunction "5_5") (pintype "passive"))
      (node (ref "JTAG") (pin "7") (pinfunction "7_7") (pintype "passive"))
      (node (ref "JTAG") (pin "9") (pinfunction "9_9") (pintype "passive"))
      (node (ref "LCD") (pin "2") (pinfunction "GND_2") (pintype "bidirectional"))
      (node (ref "M0|M1|M2|VS2|VS1|VS0") (pin "10") (pinfunction "10_10") (pintype "passive"))
      (node (ref "M0|M1|M2|VS2|VS1|VS0") (pin "11") (pinfunction "11_11") (pintype "passive"))
      (node (ref "M0|M1|M2|VS2|VS1|VS0") (pin "12") (pinfunction "12_12") (pintype "passive"))
      (node (ref "M0|M1|M2|VS2|VS1|VS0") (pin "7") (pinfunction "7_7") (pintype "passive"))
      (node (ref "M0|M1|M2|VS2|VS1|VS0") (pin "8") (pinfunction "8_8") (pintype "passive"))
      (node (ref "M0|M1|M2|VS2|VS1|VS0") (pin "9") (pinfunction "9_9") (pintype "passive"))
      (node (ref "POWER") (pin "1") (pinfunction "1_1") (pintype "passive"))
      (node (ref "PROG_B") (pin "3") (pinfunction "P_3") (pintype "passive"))
      (node (ref "PUDC_B") (pin "1") (pinfunction "1_1") (pintype "passive"))
      (node (ref "R11") (pin "1") (pinfunction "1_1") (pintype "passive"))
      (node (ref "R5") (pin "1") (pinfunction "1_1") (pintype "passive"))
      (node (ref "RESET") (pin "4") (pinfunction "P1_4") (pintype "passive"))
      (node (ref "T4") (pin "2") (pinfunction "S_2") (pintype "passive"))
      (node (ref "U$1") (pin "13") (pinfunction "GND_13") (pintype "power_in"))
      (node (ref "U$1") (pin "5") (pinfunction "GND_5") (pintype "power_in"))
      (node (ref "U1") (pin "100") (pinfunction "P100,GND,GND,GND,_100") (pintype "passive"))
      (node (ref "U1") (pin "106") (pinfunction "P106,GND,GND,GND,_106") (pintype "passive"))
      (node (ref "U1") (pin "118") (pinfunction "P118,GND,GND,GND,_118") (pintype "passive"))
      (node (ref "U1") (pin "128") (pinfunction "P128,GND,GND,GND,_128") (pintype "passive"))
      (node (ref "U1") (pin "137") (pinfunction "P137,GND,GND,GND,_137") (pintype "passive"))
      (node (ref "U1") (pin "17") (pinfunction "P17,GND,GND,GND,_17") (pintype "passive"))
      (node (ref "U1") (pin "26") (pinfunction "P26,GND,GND,GND,_26") (pintype "passive"))
      (node (ref "U1") (pin "34") (pinfunction "P34,GND,GND,GND,_34") (pintype "passive"))
      (node (ref "U1") (pin "56") (pinfunction "P56,GND,GND,GND,_56") (pintype "passive"))
      (node (ref "U1") (pin "65") (pinfunction "P65,GND,GND,GND,_65") (pintype "passive"))
      (node (ref "U1") (pin "81") (pinfunction "P81,GND,GND,GND,_81") (pintype "passive"))
      (node (ref "U1") (pin "89") (pinfunction "P89,GND,GND,GND,_89") (pintype "passive"))
      (node (ref "U1") (pin "9") (pinfunction "P9,GND,GND,GND,_9") (pintype "passive"))
      (node (ref "U2") (pin "4") (pinfunction "GND_4") (pintype "bidirectional"))
      (node (ref "U3") (pin "1") (pinfunction "GND_1") (pintype "bidirectional"))
      (node (ref "U3") (pin "12") (pinfunction "GND_12") (pintype "bidirectional"))
      (node (ref "U3") (pin "13") (pinfunction "GND_13") (pintype "bidirectional"))
      (node (ref "U3") (pin "24") (pinfunction "GND_24") (pintype "bidirectional"))
      (node (ref "U3") (pin "9") (pinfunction "GND_9") (pintype "bidirectional"))
      (node (ref "U3") (pin "EXP") (pinfunction "GND_EXP") (pintype "bidirectional"))
      (node (ref "U4") (pin "P1_14") (pinfunction "GND_P1_14") (pintype "bidirectional"))
      (node (ref "U4") (pin "P1_20") (pinfunction "GND_P1_20") (pintype "bidirectional"))
      (node (ref "U4") (pin "P1_25") (pinfunction "GND_P1_25") (pintype "bidirectional"))
      (node (ref "U4") (pin "P1_6") (pinfunction "GND_P1_6") (pintype "bidirectional"))
      (node (ref "U4") (pin "P1_9") (pinfunction "GND_P1_9") (pintype "bidirectional"))
      (node (ref "U4") (pin "P5_7") (pinfunction "GND_P5_7") (pintype "bidirectional"))
      (node (ref "U4") (pin "P5_8") (pinfunction "GND_P5_8") (pintype "bidirectional"))
      (node (ref "U4") (pin "P6_2") (pinfunction "GND_P6_2") (pintype "bidirectional"))
      (node (ref "U5") (pin "1") (pinfunction "GND_1") (pintype "input"))
      (node (ref "U6") (pin "2") (pinfunction "GND_2") (pintype "power_in"))
      (node (ref "U7") (pin "1") (pinfunction "GND_1") (pintype "input"))
      (node (ref "USB-RS232") (pin "5") (pinfunction "5_5") (pintype "passive"))
    )
    (net (code "28") (name "GPIO4,GPCLK0") (class "Default")
      (node (ref "U1") (pin "58") (pinfunction "P58,IO_L10P_2/GCLK2,2,GCLK,TRUE_58") (pintype "passive"))
      (node (ref "U4") (pin "P1_7") (pinfunction "GPIO4,GPCLK0_P1_7") (pintype "bidirectional"))
    )
    (net (code "29") (name "GPIO17") (class "Default")
      (node (ref "U1") (pin "57") (pinfunction "P57,IO_L09P_2/GCLK0,2,GCLK,TRUE_57") (pintype "passive"))
      (node (ref "U4") (pin "P1_11") (pinfunction "GPIO17_P1_11") (pintype "bidirectional"))
    )
    (net (code "30") (name "GPIO18") (class "Default")
      (node (ref "U1") (pin "54") (pinfunction "P54,IO_L08P_2/GCLK14,2,GCLK,TRUE_54") (pintype "passive"))
      (node (ref "U4") (pin "P1_12") (pinfunction "GPIO18_P1_12") (pintype "bidirectional"))
    )
    (net (code "31") (name "GPIO22") (class "Default")
      (node (ref "U1") (pin "51") (pinfunction "P51,IO_L07N_2/D4,2,DUAL,TRUE_51") (pintype "passive"))
      (node (ref "U4") (pin "P1_15") (pinfunction "GPIO22_P1_15") (pintype "bidirectional"))
    )
    (net (code "32") (name "GPIO23") (class "Default")
      (node (ref "U1") (pin "50") (pinfunction "P50,IO_L07P_2/D5,2,DUAL,TRUE_50") (pintype "passive"))
      (node (ref "U4") (pin "P1_16") (pinfunction "GPIO23_P1_16") (pintype "bidirectional"))
    )
    (net (code "33") (name "GPIO24") (class "Default")
      (node (ref "U1") (pin "49") (pinfunction "P49,IO_L06N_2/D6,2,DUAL,TRUE_49") (pintype "passive"))
      (node (ref "U4") (pin "P1_18") (pinfunction "GPIO24_P1_18") (pintype "bidirectional"))
    )
    (net (code "34") (name "GPIO25") (class "Default")
      (node (ref "U1") (pin "48") (pinfunction "P48,IO_L05N_2/D7,2,DUAL,TRUE_48") (pintype "passive"))
      (node (ref "U4") (pin "P1_22") (pinfunction "GPIO25_P1_22") (pintype "bidirectional"))
    )
    (net (code "35") (name "GPIO27") (class "Default")
      (node (ref "U1") (pin "55") (pinfunction "P55,IO_L08N_2/GCLK15,2,GCLK,TRUE_55") (pintype "passive"))
      (node (ref "U4") (pin "P1_13") (pinfunction "GPIO27_P1_13") (pintype "bidirectional"))
    )
    (net (code "36") (name "GPIO28") (class "Default")
      (node (ref "U1") (pin "69") (pinfunction "P69,IO_L13P_2/D2,2,DUAL,TRUE_69") (pintype "passive"))
      (node (ref "U4") (pin "P5_3") (pinfunction "GPIO28_P5_3") (pintype "bidirectional"))
    )
    (net (code "37") (name "GPIO29") (class "Default")
      (node (ref "U1") (pin "70") (pinfunction "P70,IO_L14P_2/D1,2,DUAL,TRUE_70") (pintype "passive"))
      (node (ref "U4") (pin "P5_4") (pinfunction "GPIO29_P5_4") (pintype "bidirectional"))
    )
    (net (code "38") (name "GPIO30") (class "Default")
      (node (ref "U1") (pin "64") (pinfunction "P64,IO_L11N_2/DOUT,2,DUAL,TRUE_64") (pintype "passive"))
      (node (ref "U4") (pin "P5_5") (pinfunction "GPIO30_P5_5") (pintype "bidirectional"))
    )
    (net (code "39") (name "GPIO31") (class "Default")
      (node (ref "U1") (pin "68") (pinfunction "P68,IO_L12N_2/D3,2,DUAL,TRUE_68") (pintype "passive"))
      (node (ref "U4") (pin "P5_6") (pinfunction "GPIO31_P5_6") (pintype "bidirectional"))
    )
    (net (code "40") (name "INIT_B") (class "Default")
      (node (ref "R3") (pin "2") (pinfunction "2_2") (pintype "passive"))
      (node (ref "R4") (pin "2") (pinfunction "2_2") (pintype "passive"))
      (node (ref "U1") (pin "67") (pinfunction "P67,IO_L12P_2/INIT_B,2,DUAL,TRUE_67") (pintype "passive"))
    )
    (net (code "41") (name "INT") (class "Default")
      (node (ref "LCD") (pin "26") (pinfunction "TP_PEN_INT_26") (pintype "bidirectional"))
      (node (ref "U1") (pin "97") (pinfunction "P97,IP_1/VREF_1,1,VREF,_97") (pintype "passive"))
    )
    (net (code "42") (name "IO_0") (class "Default")
      (node (ref "BANK0") (pin "2") (pinfunction "2_2") (pintype "passive"))
      (node (ref "U1") (pin "142") (pinfunction "P142,IO_0,0,I/O,_142") (pintype "passive"))
    )
    (net (code "43") (name "IO_L01N_0") (class "Default")
      (node (ref "BANK0") (pin "34") (pinfunction "34_34") (pintype "passive"))
      (node (ref "U1") (pin "111") (pinfunction "P111,IO_L01N_0,0,I/O,TRUE_111") (pintype "passive"))
    )
    (net (code "44") (name "IO_L01N_3") (class "Default")
      (node (ref "BANK3") (pin "35") (pinfunction "35_35") (pintype "passive"))
      (node (ref "U1") (pin "6") (pinfunction "P6,IO_L01N_3,3,I/O,TRUE_6") (pintype "passive"))
    )
    (net (code "45") (name "IO_L01P_3") (class "Default")
      (node (ref "BANK3") (pin "37") (pinfunction "37_37") (pintype "passive"))
      (node (ref "U1") (pin "4") (pinfunction "P4,IO_L01P_3,3,I/O,TRUE_4") (pintype "passive"))
    )
    (net (code "46") (name "IO_L02N_0") (class "Default")
      (node (ref "BANK0") (pin "32") (pinfunction "32_32") (pintype "passive"))
      (node (ref "U1") (pin "113") (pinfunction "P113,IO_L02N_0,0,I/O,TRUE_113") (pintype "passive"))
    )
    (net (code "47") (name "IO_L02N_3") (class "Default")
      (node (ref "BANK3") (pin "36") (pinfunction "36_36") (pintype "passive"))
      (node (ref "U1") (pin "5") (pinfunction "P5,IO_L02N_3,3,I/O,TRUE_5") (pintype "passive"))
    )
    (net (code "48") (name "IO_L02P_0{slash}VREF_0") (class "Default")
      (node (ref "BANK0") (pin "31") (pinfunction "31_31") (pintype "passive"))
      (node (ref "U1") (pin "112") (pinfunction "P112,IO_L02P_0/VREF_0,0,VREF,TRUE_112") (pintype "passive"))
    )
    (net (code "49") (name "IO_L02P_3") (class "Default")
      (node (ref "BANK3") (pin "38") (pinfunction "38_38") (pintype "passive"))
      (node (ref "U1") (pin "3") (pinfunction "P3,IO_L02P_3,3,I/O,TRUE_3") (pintype "passive"))
    )
    (net (code "50") (name "IO_L03N_0") (class "Default")
      (node (ref "BANK0") (pin "26") (pinfunction "26_26") (pintype "passive"))
      (node (ref "U1") (pin "117") (pinfunction "P117,IO_L03N_0,0,I/O,TRUE_117") (pintype "passive"))
    )
    (net (code "51") (name "IO_L03N_3") (class "Default")
      (node (ref "BANK3") (pin "33") (pinfunction "33_33") (pintype "passive"))
      (node (ref "U1") (pin "8") (pinfunction "P8,IO_L03N_3,3,I/O,TRUE_8") (pintype "passive"))
    )
    (net (code "52") (name "IO_L03P_0") (class "Default")
      (node (ref "BANK0") (pin "28") (pinfunction "28_28") (pintype "passive"))
      (node (ref "U1") (pin "115") (pinfunction "P115,IO_L03P_0,0,I/O,TRUE_115") (pintype "passive"))
    )
    (net (code "53") (name "IO_L03P_3") (class "Default")
      (node (ref "BANK3") (pin "34") (pinfunction "34_34") (pintype "passive"))
      (node (ref "U1") (pin "7") (pinfunction "P7,IO_L03P_3,3,I/O,TRUE_7") (pintype "passive"))
    )
    (net (code "54") (name "IO_L04N_0") (class "Default")
      (node (ref "BANK0") (pin "25") (pinfunction "25_25") (pintype "passive"))
      (node (ref "U1") (pin "116") (pinfunction "P116,IO_L04N_0,0,I/O,TRUE_116") (pintype "passive"))
    )
    (net (code "55") (name "IO_L04N_3{slash}VREF_3") (class "Default")
      (node (ref "BANK3") (pin "29") (pinfunction "29_29") (pintype "passive"))
      (node (ref "U1") (pin "11") (pinfunction "P11,IO_L04N_3/VREF_3,3,VREF,TRUE_11") (pintype "passive"))
    )
    (net (code "56") (name "IO_L04P_0") (class "Default")
      (node (ref "BANK0") (pin "27") (pinfunction "27_27") (pintype "passive"))
      (node (ref "U1") (pin "114") (pinfunction "P114,IO_L04P_0,0,I/O,TRUE_114") (pintype "passive"))
    )
    (net (code "57") (name "IO_L04P_3") (class "Default")
      (node (ref "BANK3") (pin "30") (pinfunction "30_30") (pintype "passive"))
      (node (ref "U1") (pin "10") (pinfunction "P10,IO_L04P_3,3,I/O,TRUE_10") (pintype "passive"))
    )
    (net (code "58") (name "IO_L05N_0") (class "Default")
      (node (ref "BANK0") (pin "24") (pinfunction "24_24") (pintype "passive"))
      (node (ref "U1") (pin "121") (pinfunction "P121,IO_L05N_0,0,I/O,TRUE_121") (pintype "passive"))
    )
    (net (code "59") (name "IO_L05P_0") (class "Default")
      (node (ref "BANK0") (pin "23") (pinfunction "23_23") (pintype "passive"))
      (node (ref "U1") (pin "120") (pinfunction "P120,IO_L05P_0,0,I/O,TRUE_120") (pintype "passive"))
    )
    (net (code "60") (name "IO_L06N_0{slash}GCLK5") (class "Default")
      (node (ref "BANK0") (pin "18") (pinfunction "18_18") (pintype "passive"))
      (node (ref "U1") (pin "126") (pinfunction "P126,IO_L06N_0/GCLK5,0,GCLK,TRUE_126") (pintype "passive"))
    )
    (net (code "61") (name "IO_L06P_0{slash}GCLK4") (class "Default")
      (node (ref "BANK0") (pin "20") (pinfunction "20_20") (pintype "passive"))
      (node (ref "U1") (pin "124") (pinfunction "P124,IO_L06P_0/GCLK4,0,GCLK,TRUE_124") (pintype "passive"))
    )
    (net (code "62") (name "IO_L08N_0{slash}GCLK9") (class "Default")
      (node (ref "BANK0") (pin "12") (pinfunction "12_12") (pintype "passive"))
      (node (ref "U1") (pin "131") (pinfunction "P131,IO_L08N_0/GCLK9,0,GCLK,TRUE_131") (pintype "passive"))
    )
    (net (code "63") (name "IO_L08P_0{slash}GCLK8") (class "Default")
      (node (ref "U1") (pin "129") (pinfunction "P129,IO_L08P_0/GCLK8,0,GCLK,TRUE_129") (pintype "passive"))
      (node (ref "USR_CLK") (pin "2") (pinfunction "2_2") (pintype "passive"))
    )
    (net (code "64") (name "IO_L10N_3") (class "Default")
      (node (ref "BANK3") (pin "12") (pinfunction "12_12") (pintype "passive"))
      (node (ref "U1") (pin "29") (pinfunction "P29,IO_L10N_3,3,I/O,TRUE_29") (pintype "passive"))
    )
    (net (code "65") (name "IO_L10P_3") (class "Default")
      (node (ref "BANK3") (pin "14") (pinfunction "14_14") (pintype "passive"))
      (node (ref "U1") (pin "27") (pinfunction "P27,IO_L10P_3,3,I/O,TRUE_27") (pintype "passive"))
    )
    (net (code "66") (name "IO_L11N_0") (class "Default")
      (node (ref "BANK0") (pin "3") (pinfunction "3_3") (pintype "passive"))
      (node (ref "U1") (pin "139") (pinfunction "P139,IO_L11N_0,0,I/O,TRUE_139") (pintype "passive"))
    )
    (net (code "67") (name "IO_L11N_3") (class "Default")
      (node (ref "BANK3") (pin "11") (pinfunction "11_11") (pintype "passive"))
      (node (ref "U1") (pin "30") (pinfunction "P30,IO_L11N_3,3,I/O,TRUE_30") (pintype "passive"))
    )
    (net (code "68") (name "IO_L11P_0") (class "Default")
      (node (ref "BANK0") (pin "6") (pinfunction "6_6") (pintype "passive"))
      (node (ref "U1") (pin "138") (pinfunction "P138,IO_L11P_0,0,I/O,TRUE_138") (pintype "passive"))
    )
    (net (code "69") (name "IO_L11P_3") (class "Default")
      (node (ref "BANK3") (pin "13") (pinfunction "13_13") (pintype "passive"))
      (node (ref "U1") (pin "28") (pinfunction "P28,IO_L11P_3,3,I/O,TRUE_28") (pintype "passive"))
    )
    (net (code "70") (name "IO_L12N_3") (class "Default")
      (node (ref "BANK3") (pin "7") (pinfunction "7_7") (pintype "passive"))
      (node (ref "U1") (pin "32") (pinfunction "P32,IO_L12N_3,3,I/O,TRUE_32") (pintype "passive"))
    )
    (net (code "71") (name "IO_L12P_0{slash}VREF_0") (class "Default")
      (node (ref "BANK0") (pin "1") (pinfunction "1_1") (pintype "passive"))
      (node (ref "U1") (pin "141") (pinfunction "P141,IO_L12P_0/VREF_0,0,VREF,TRUE_141") (pintype "passive"))
    )
    (net (code "72") (name "IO_L12P_3") (class "Default")
      (node (ref "BANK3") (pin "8") (pinfunction "8_8") (pintype "passive"))
      (node (ref "U1") (pin "31") (pinfunction "P31,IO_L12P_3,3,I/O,TRUE_31") (pintype "passive"))
    )
    (net (code "73") (name "IP_0") (class "Default")
      (node (ref "BANK0") (pin "4") (pinfunction "4_4") (pintype "passive"))
      (node (ref "U1") (pin "140") (pinfunction "P140,IP_0,0,INPUT,_140") (pintype "passive"))
    )
    (net (code "74") (name "IP_0{slash}VREF_0") (class "Default")
      (node (ref "BANK0") (pin "21") (pinfunction "21_21") (pintype "passive"))
      (node (ref "U1") (pin "123") (pinfunction "P123,IP_0/VREF_0,0,VREF,_123") (pintype "passive"))
    )
    (net (code "75") (name "IP_1{slash}VREF_1") (class "Default")
      (node (ref "U1") (pin "80") (pinfunction "P80,IP_1/VREF_1,1,VREF,_80") (pintype "passive"))
    )
    (net (code "76") (name "IP_L13N_3{slash}VREF_3") (class "Default")
      (node (ref "BANK3") (pin "5") (pinfunction "5_5") (pintype "passive"))
      (node (ref "U1") (pin "35") (pinfunction "P35,IP_L13N_3/VREF_3,3,VREF,TRUE_35") (pintype "passive"))
    )
    (net (code "77") (name "IP_L13P_3") (class "Default")
      (node (ref "BANK3") (pin "6") (pinfunction "6_6") (pintype "passive"))
      (node (ref "U1") (pin "33") (pinfunction "P33,IP_L13P_3,3,INPUT,TRUE_33") (pintype "passive"))
    )
    (net (code "78") (name "LCD3,3V") (class "Default")
      (node (ref "LCD") (pin "1") (pinfunction "3V3_1") (pintype "bidirectional"))
      (node (ref "U5") (pin "2") (pinfunction "OUT_2") (pintype "passive"))
      (node (ref "U5") (pin "TAB") (pinfunction "OUT1_TAB") (pintype "passive"))
    )
    (net (code "79") (name "LCD_B0") (class "Default")
      (node (ref "LCD") (pin "3") (pinfunction "DB00_3") (pintype "bidirectional"))
      (node (ref "U1") (pin "77") (pinfunction "P77,IO_L02N_1/LDC0,1,DUAL,TRUE_77") (pintype "passive"))
    )
    (net (code "80") (name "LCD_B1") (class "Default")
      (node (ref "LCD") (pin "4") (pinfunction "DB01_4") (pintype "bidirectional"))
      (node (ref "U1") (pin "78") (pinfunction "P78,IO_L01N_1/LDC2,1,DUAL,TRUE_78") (pintype "passive"))
    )
    (net (code "81") (name "LCD_B2") (class "Default")
      (node (ref "LCD") (pin "5") (pinfunction "DB02_5") (pintype "bidirectional"))
      (node (ref "U1") (pin "79") (pinfunction "P79,IO_1,1,I/O,_79") (pintype "passive"))
    )
    (net (code "82") (name "LCD_B3") (class "Default")
      (node (ref "LCD") (pin "6") (pinfunction "DB03_6") (pintype "bidirectional"))
      (node (ref "U1") (pin "82") (pinfunction "P82,IO_L03P_1,1,I/O,TRUE_82") (pintype "passive"))
    )
    (net (code "83") (name "LCD_B4") (class "Default")
      (node (ref "LCD") (pin "7") (pinfunction "DB04_7") (pintype "bidirectional"))
      (node (ref "U1") (pin "83") (pinfunction "P83,IO_L04P_1/RHCLK0,1,RHCLK,TRUE_83") (pintype "passive"))
    )
    (net (code "84") (name "LCD_B5") (class "Default")
      (node (ref "LCD") (pin "8") (pinfunction "DB05_8") (pintype "bidirectional"))
      (node (ref "U1") (pin "84") (pinfunction "P84,IO_L03N_1,1,I/O,TRUE_84") (pintype "passive"))
    )
    (net (code "85") (name "LCD_B6") (class "Default")
      (node (ref "LCD") (pin "9") (pinfunction "DB06_9") (pintype "bidirectional"))
      (node (ref "U1") (pin "85") (pinfunction "P85,IO_L04N_1/RHCLK1,1,RHCLK,TRUE_85") (pintype "passive"))
    )
    (net (code "86") (name "LCD_B7") (class "Default")
      (node (ref "LCD") (pin "10") (pinfunction "DB07_10") (pintype "bidirectional"))
      (node (ref "U1") (pin "87") (pinfunction "P87,IO_L05P_1/RHCLK2,1,RHCLK,TRUE_87") (pintype "passive"))
    )
    (net (code "87") (name "LCD_B8") (class "Default")
      (node (ref "LCD") (pin "11") (pinfunction "DB08_11") (pintype "bidirectional"))
      (node (ref "U1") (pin "88") (pinfunction "P88,IO_L05N_1/TRDY1/RHCLK3,1,RHCLK,TRUE_88") (pintype "passive"))
    )
    (net (code "88") (name "LCD_B9") (class "Default")
      (node (ref "LCD") (pin "12") (pinfunction "DB09_12") (pintype "bidirectional"))
      (node (ref "U1") (pin "96") (pinfunction "P96,IO_L08P_1,1,I/O,TRUE_96") (pintype "passive"))
    )
    (net (code "89") (name "LCD_B10") (class "Default")
      (node (ref "LCD") (pin "13") (pinfunction "DB10_13") (pintype "bidirectional"))
      (node (ref "U1") (pin "98") (pinfunction "P98,IO_L08N_1,1,I/O,TRUE_98") (pintype "passive"))
    )
    (net (code "90") (name "LCD_B11") (class "Default")
      (node (ref "LCD") (pin "14") (pinfunction "DB11_14") (pintype "bidirectional"))
      (node (ref "U1") (pin "99") (pinfunction "P99,IO_L09P_1,1,I/O,TRUE_99") (pintype "passive"))
    )
    (net (code "91") (name "LCD_B12") (class "Default")
      (node (ref "LCD") (pin "15") (pinfunction "DB12_15") (pintype "bidirectional"))
      (node (ref "U1") (pin "101") (pinfunction "P101,IO_L09N_1,1,I/O,TRUE_101") (pintype "passive"))
    )
    (net (code "92") (name "LCD_B13") (class "Default")
      (node (ref "LCD") (pin "16") (pinfunction "DB13_16") (pintype "bidirectional"))
      (node (ref "U1") (pin "102") (pinfunction "P102,IO_L10P_1,1,I/O,TRUE_102") (pintype "passive"))
    )
    (net (code "93") (name "LCD_B14") (class "Default")
      (node (ref "LCD") (pin "17") (pinfunction "DB14_17") (pintype "bidirectional"))
      (node (ref "U1") (pin "103") (pinfunction "P103,IO_L11P_1,1,I/O,TRUE_103") (pintype "passive"))
    )
    (net (code "94") (name "LCD_B15") (class "Default")
      (node (ref "LCD") (pin "18") (pinfunction "DB15_18") (pintype "bidirectional"))
      (node (ref "U1") (pin "104") (pinfunction "P104,IO_L10N_1,1,I/O,TRUE_104") (pintype "passive"))
    )
    (net (code "95") (name "M0") (class "Default")
      (node (ref "M0|M1|M2|VS2|VS1|VS0") (pin "5") (pinfunction "5_5") (pintype "passive"))
      (node (ref "U1") (pin "38") (pinfunction "P38,IO_L01N_2/M0,2,DUAL,TRUE_38") (pintype "passive"))
    )
    (net (code "96") (name "M1") (class "Default")
      (node (ref "M0|M1|M2|VS2|VS1|VS0") (pin "6") (pinfunction "6_6") (pintype "passive"))
      (node (ref "U1") (pin "37") (pinfunction "P37,IO_L01P_2/M1,2,DUAL,TRUE_37") (pintype "passive"))
    )
    (net (code "97") (name "M2") (class "Default")
      (node (ref "M0|M1|M2|VS2|VS1|VS0") (pin "4") (pinfunction "4_4") (pintype "passive"))
      (node (ref "U1") (pin "39") (pinfunction "P39,IO_L02P_2/M2,2,DUAL,TRUE_39") (pintype "passive"))
    )
    (net (code "98") (name "Net-(C20-Pad2)") (class "Default")
      (node (ref "C20") (pin "2") (pinfunction "2_2") (pintype "passive"))
      (node (ref "R9") (pin "1") (pinfunction "1_1") (pintype "passive"))
    )
    (net (code "99") (name "Net-(C25-Pad1)") (class "Default")
      (node (ref "C25") (pin "1") (pinfunction "1_1") (pintype "passive"))
      (node (ref "L1") (pin "2") (pinfunction "2_2") (pintype "passive"))
      (node (ref "USB-RS232") (pin "1") (pinfunction "1_1") (pintype "passive"))
    )
    (net (code "100") (name "Net-(C34-Pad2)") (class "Default")
      (node (ref "C34") (pin "2") (pinfunction "2_2") (pintype "passive"))
      (node (ref "R17") (pin "2") (pinfunction "2_2") (pintype "passive"))
      (node (ref "USB-RS232") (pin "3") (pinfunction "3_3") (pintype "passive"))
    )
    (net (code "101") (name "Net-(C35-Pad2)") (class "Default")
      (node (ref "C35") (pin "2") (pinfunction "2_2") (pintype "passive"))
      (node (ref "R18") (pin "2") (pinfunction "2_2") (pintype "passive"))
      (node (ref "USB-RS232") (pin "2") (pinfunction "2_2") (pintype "passive"))
    )
    (net (code "102") (name "Net-(DONE-PadC)") (class "Default")
      (node (ref "DONE") (pin "C") (pinfunction "C_C") (pintype "passive"))
      (node (ref "R5") (pin "2") (pinfunction "2_2") (pintype "passive"))
    )
    (net (code "103") (name "Net-(F1-Pad2)") (class "Default")
      (node (ref "F1") (pin "2") (pinfunction "2_2") (pintype "passive"))
      (node (ref "U4") (pin "P1_2") (pinfunction "5V_P1_2") (pintype "bidirectional"))
      (node (ref "U4") (pin "P1_4") (pinfunction "5V_P1_4") (pintype "bidirectional"))
    )
    (net (code "104") (name "Net-(INIT-PadC)") (class "Default")
      (node (ref "INIT") (pin "C") (pinfunction "C_C") (pintype "passive"))
      (node (ref "R4") (pin "1") (pinfunction "1_1") (pintype "passive"))
    )
    (net (code "105") (name "Net-(PUDC_B-Pad3)") (class "Default")
      (node (ref "PUDC_B") (pin "3") (pinfunction "3_3") (pintype "passive"))
      (node (ref "R16") (pin "2") (pinfunction "2_2") (pintype "passive"))
    )
    (net (code "106") (name "Net-(R12-Pad1)") (class "Default")
      (node (ref "R12") (pin "1") (pinfunction "1_1") (pintype "passive"))
      (node (ref "TXD") (pin "A") (pinfunction "A_A") (pintype "passive"))
    )
    (net (code "107") (name "Net-(R13-Pad1)") (class "Default")
      (node (ref "R13") (pin "1") (pinfunction "1_1") (pintype "passive"))
      (node (ref "RXD") (pin "A") (pinfunction "A_A") (pintype "passive"))
    )
    (net (code "108") (name "Net-(T3-D)") (class "Default")
      (node (ref "C19") (pin "+") (pinfunction "+_+") (pintype "passive"))
      (node (ref "C20") (pin "1") (pinfunction "1_1") (pintype "passive"))
      (node (ref "T3") (pin "1") (pinfunction "D1_1") (pintype "passive"))
      (node (ref "T3") (pin "2") (pinfunction "D2_2") (pintype "passive"))
      (node (ref "T3") (pin "5") (pinfunction "D3_5") (pintype "passive"))
      (node (ref "T3") (pin "6") (pinfunction "D_6") (pintype "passive"))
      (node (ref "TP1") (pin "PP") (pinfunction "TP_PP") (pintype "input"))
      (node (ref "U3") (pin "21") (pinfunction "VSENSE1_21") (pintype "bidirectional"))
      (node (ref "U3") (pin "22") (pinfunction "VOUT1_22") (pintype "bidirectional"))
      (node (ref "U3") (pin "23") (pinfunction "VOUT1_23") (pintype "bidirectional"))
    )
    (net (code "109") (name "Net-(T3-G)") (class "Default")
      (node (ref "C22") (pin "1") (pinfunction "1_1") (pintype "passive"))
      (node (ref "R8") (pin "1") (pinfunction "1_1") (pintype "passive"))
      (node (ref "R9") (pin "2") (pinfunction "2_2") (pintype "passive"))
      (node (ref "T3") (pin "3") (pinfunction "G_3") (pintype "passive"))
      (node (ref "U3") (pin "19") (pinfunction "PG1_19") (pintype "bidirectional"))
    )
    (net (code "110") (name "Net-(T4-D)") (class "Default")
      (node (ref "R14") (pin "1") (pinfunction "1_1") (pintype "passive"))
      (node (ref "T4") (pin "3") (pinfunction "D_3") (pintype "passive"))
      (node (ref "U3") (pin "6") (pinfunction "EN1_6") (pintype "bidirectional"))
      (node (ref "U3") (pin "7") (pinfunction "EN2_7") (pintype "bidirectional"))
    )
    (net (code "111") (name "Net-(T4-G)") (class "Default")
      (node (ref "C26") (pin "1") (pinfunction "1_1") (pintype "passive"))
      (node (ref "R15") (pin "1") (pinfunction "1_1") (pintype "passive"))
      (node (ref "T4") (pin "1") (pinfunction "G_1") (pintype "passive"))
    )
    (net (code "112") (name "Net-(U$1-3V3OUT)") (class "Default")
      (node (ref "C24") (pin "2") (pinfunction "2_2") (pintype "passive"))
      (node (ref "R12") (pin "2") (pinfunction "2_2") (pintype "passive"))
      (node (ref "R13") (pin "2") (pinfunction "2_2") (pintype "passive"))
      (node (ref "U$1") (pin "10") (pinfunction "3V3OUT_10") (pintype "output"))
      (node (ref "U$1") (pin "11") (pinfunction "~{RESET}_11") (pintype "input"))
      (node (ref "U$1") (pin "3") (pinfunction "VCCIO_3") (pintype "power_in"))
    )
    (net (code "113") (name "Net-(U$1-CBUS1)") (class "Default")
      (node (ref "TXD") (pin "C") (pinfunction "C_C") (pintype "passive"))
      (node (ref "U$1") (pin "14") (pinfunction "CBUS1_14") (pintype "bidirectional"))
    )
    (net (code "114") (name "Net-(U$1-CBUS2)") (class "Default")
      (node (ref "RXD") (pin "C") (pinfunction "C_C") (pintype "passive"))
      (node (ref "U$1") (pin "7") (pinfunction "CBUS2_7") (pintype "bidirectional"))
    )
    (net (code "115") (name "Net-(U$1-USBDM)") (class "Default")
      (node (ref "R18") (pin "1") (pinfunction "1_1") (pintype "passive"))
      (node (ref "U$1") (pin "9") (pinfunction "USBDM_9") (pintype "bidirectional"))
    )
    (net (code "116") (name "Net-(U$1-USBDP)") (class "Default")
      (node (ref "R17") (pin "1") (pinfunction "1_1") (pintype "passive"))
      (node (ref "U$1") (pin "8") (pinfunction "USBDP_8") (pintype "bidirectional"))
    )
    (net (code "117") (name "Net-(U2-VBAT)") (class "Default")
      (node (ref "BATT") (pin "+") (pinfunction "+_+") (pintype "passive"))
      (node (ref "U2") (pin "3") (pinfunction "VBAT_3") (pintype "bidirectional"))
    )
    (net (code "118") (name "Net-(U2-X1)") (class "Default")
      (node (ref "Q1") (pin "2") (pinfunction "2_2") (pintype "passive"))
      (node (ref "U2") (pin "1") (pinfunction "X1_1") (pintype "bidirectional"))
    )
    (net (code "119") (name "Net-(U2-X2)") (class "Default")
      (node (ref "Q1") (pin "1") (pinfunction "1_1") (pintype "passive"))
      (node (ref "U2") (pin "2") (pinfunction "X2_2") (pintype "bidirectional"))
    )
    (net (code "120") (name "Net-(U3-VSENSE2)") (class "Default")
      (node (ref "R10") (pin "1") (pinfunction "1_1") (pintype "passive"))
      (node (ref "R11") (pin "2") (pinfunction "2_2") (pintype "passive"))
      (node (ref "U3") (pin "16") (pinfunction "VSENSE2_16") (pintype "bidirectional"))
    )
    (net (code "121") (name "PROG_B") (class "Default")
      (node (ref "PROG_B") (pin "1") (pinfunction "S_1") (pintype "passive"))
      (node (ref "R1") (pin "1") (pinfunction "1_1") (pintype "passive"))
      (node (ref "U1") (pin "144") (pinfunction "P144,PROG_B,VCCAUX,CONFIG,_144") (pintype "passive"))
    )
    (net (code "122") (name "PUDC_B") (class "Default")
      (node (ref "PUDC_B") (pin "2") (pinfunction "2_2") (pintype "passive"))
      (node (ref "U1") (pin "143") (pinfunction "P143,IO_L12N_0/PUDC_B,0,DUAL,TRUE_143") (pintype "passive"))
    )
    (net (code "123") (name "RD") (class "Default")
      (node (ref "LCD") (pin "22") (pinfunction "RD_22") (pintype "bidirectional"))
      (node (ref "U1") (pin "93") (pinfunction "P93,IO_L07N_1/RHCLK7,1,RHCLK,TRUE_93") (pintype "passive"))
    )
    (net (code "124") (name "RES") (class "Default")
      (node (ref "LCD") (pin "23") (pinfunction "RESET_23") (pintype "bidirectional"))
      (node (ref "RESET") (pin "2") (pinfunction "S1_2") (pintype "passive"))
      (node (ref "U4") (pin "P6_1") (pinfunction "RES_P6_1") (pintype "bidirectional"))
    )
    (net (code "125") (name "RS") (class "Default")
      (node (ref "LCD") (pin "20") (pinfunction "RS_20") (pintype "bidirectional"))
      (node (ref "U1") (pin "91") (pinfunction "P91,IO_L07P_1/IRDY1/RHCLK6,1,RHCLK,TRUE_91") (pintype "passive"))
    )
    (net (code "126") (name "RS232_RXD") (class "Default")
      (node (ref "U$1") (pin "1") (pinfunction "TXD_1") (pintype "output"))
      (node (ref "U1") (pin "75") (pinfunction "P75,IO_L02P_1/LDC1,1,DUAL,TRUE_75") (pintype "passive"))
    )
    (net (code "127") (name "RS232_RX_PI") (class "Default")
      (node (ref "U1") (pin "47") (pinfunction "P47,IO_L06P_2,2,I/O,TRUE_47") (pintype "passive"))
      (node (ref "U4") (pin "P1_10") (pinfunction "GPIO15,UART0_RXD_P1_10") (pintype "bidirectional"))
    )
    (net (code "128") (name "RS232_TXD") (class "Default")
      (node (ref "U$1") (pin "4") (pinfunction "RXD_4") (pintype "input"))
      (node (ref "U1") (pin "76") (pinfunction "P76,IO_L01P_1/HDC,1,DUAL,TRUE_76") (pintype "passive"))
    )
    (net (code "129") (name "RS232_TX_PI") (class "Default")
      (node (ref "U1") (pin "46") (pinfunction "P46,IO_L05P_2,2,I/O,TRUE_46") (pintype "passive"))
      (node (ref "U4") (pin "P1_8") (pinfunction "GPIO14,UART0_TXD_P1_8") (pintype "bidirectional"))
    )
    (net (code "130") (name "SCL0") (class "Default")
      (node (ref "BANK3") (pin "2") (pinfunction "2_2") (pintype "passive"))
      (node (ref "T2") (pin "2") (pinfunction "S_2") (pintype "passive"))
      (node (ref "U1") (pin "59") (pinfunction "P59,IO_L09N_2/GCLK1,2,GCLK,TRUE_59") (pintype "passive"))
      (node (ref "U4") (pin "P1_5") (pinfunction "GPIO3,I2C0_SCL_P1_5") (pintype "bidirectional"))
    )
    (net (code "131") (name "SCL0_5V") (class "Default")
      (node (ref "R7") (pin "1") (pinfunction "1_1") (pintype "passive"))
      (node (ref "T2") (pin "3") (pinfunction "D_3") (pintype "passive"))
      (node (ref "U2") (pin "6") (pinfunction "SCL_6") (pintype "bidirectional"))
    )
    (net (code "132") (name "SDA0") (class "Default")
      (node (ref "BANK3") (pin "1") (pinfunction "1_1") (pintype "passive"))
      (node (ref "T1") (pin "2") (pinfunction "S_2") (pintype "passive"))
      (node (ref "U1") (pin "60") (pinfunction "P60,IO_L10N_2/GCLK3,2,GCLK,TRUE_60") (pintype "passive"))
      (node (ref "U4") (pin "P1_3") (pinfunction "GPIO2,I2C0_SDA_P1_3") (pintype "bidirectional"))
    )
    (net (code "133") (name "SDA0_5V") (class "Default")
      (node (ref "R6") (pin "1") (pinfunction "1_1") (pintype "passive"))
      (node (ref "T1") (pin "3") (pinfunction "D_3") (pintype "passive"))
      (node (ref "U2") (pin "5") (pinfunction "SDA_5") (pintype "bidirectional"))
    )
    (net (code "134") (name "SPI_CE0") (class "Default")
      (node (ref "U1") (pin "41") (pinfunction "P41,IO_L02N_2/CSO_B,2,DUAL,TRUE_41") (pintype "passive"))
      (node (ref "U4") (pin "P1_24") (pinfunction "GPIO8,SPI0_CE0_P1_24") (pintype "bidirectional"))
    )
    (net (code "135") (name "SPI_CE1") (class "Default")
      (node (ref "LCD") (pin "31") (pinfunction "TP_CS_31") (pintype "bidirectional"))
      (node (ref "U4") (pin "P1_26") (pinfunction "GPIO7,SPI0_CE1_P1_26") (pintype "bidirectional"))
    )
    (net (code "136") (name "SPI_CLK") (class "Default")
      (node (ref "LCD") (pin "29") (pinfunction "SCLK_SPI_29") (pintype "bidirectional"))
      (node (ref "U1") (pin "72") (pinfunction "P72,IO_L14N_2/CCLK,2,DUAL,TRUE_72") (pintype "passive"))
      (node (ref "U4") (pin "P1_23") (pinfunction "GPIO11_SCLK_P1_23") (pintype "bidirectional"))
    )
    (net (code "137") (name "SPI_MISO") (class "Default")
      (node (ref "LCD") (pin "27") (pinfunction "MOSI_SPI_27") (pintype "bidirectional"))
      (node (ref "U1") (pin "71") (pinfunction "P71,IO_L13N_2/D0/DIN/MISO,2,DUAL,TRUE_71") (pintype "passive"))
      (node (ref "U4") (pin "P1_21") (pinfunction "GPIO9_MISO_P1_21") (pintype "bidirectional"))
    )
    (net (code "138") (name "SPI_MOSI") (class "Default")
      (node (ref "LCD") (pin "25") (pinfunction "MISO_SPI_25") (pintype "bidirectional"))
      (node (ref "U1") (pin "62") (pinfunction "P62,IO_2/MOSI/CSI_B,2,DUAL,_62") (pintype "passive"))
      (node (ref "U4") (pin "P1_19") (pinfunction "GPIO10_MOSI_P1_19") (pintype "bidirectional"))
    )
    (net (code "139") (name "SPI_SD_CE") (class "Default")
      (node (ref "BANK0") (pin "33") (pinfunction "33_33") (pintype "passive"))
      (node (ref "LCD") (pin "32") (pinfunction "SD_CS_32") (pintype "bidirectional"))
      (node (ref "U1") (pin "110") (pinfunction "P110,IO_L01P_0,0,I/O,TRUE_110") (pintype "passive"))
    )
    (net (code "140") (name "SUSPEND") (class "Default")
      (node (ref "BANK3") (pin "4") (pinfunction "4_4") (pintype "passive"))
      (node (ref "U1") (pin "74") (pinfunction "P74,SUSPEND,VCCAUX,PWRMGMT,_74") (pintype "passive"))
    )
    (net (code "141") (name "TCK") (class "Default")
      (node (ref "JTAG") (pin "6") (pinfunction "6_6") (pintype "passive"))
      (node (ref "U1") (pin "109") (pinfunction "P109,TCK,VCCAUX,JTAG,_109") (pintype "passive"))
    )
    (net (code "142") (name "TDI") (class "Default")
      (node (ref "JTAG") (pin "10") (pinfunction "10_10") (pintype "passive"))
      (node (ref "U1") (pin "2") (pinfunction "P2,TDI,VCCAUX,JTAG,_2") (pintype "passive"))
    )
    (net (code "143") (name "TDO") (class "Default")
      (node (ref "JTAG") (pin "8") (pinfunction "8_8") (pintype "passive"))
      (node (ref "U1") (pin "107") (pinfunction "P107,TDO,VCCAUX,JTAG,_107") (pintype "passive"))
    )
    (net (code "144") (name "TMS") (class "Default")
      (node (ref "JTAG") (pin "4") (pinfunction "4_4") (pintype "passive"))
      (node (ref "U1") (pin "1") (pinfunction "P1,TMS,VCCAUX,JTAG,_1") (pintype "passive"))
    )
    (net (code "145") (name "USB+5V") (class "Default")
      (node (ref "L1") (pin "1") (pinfunction "1_1") (pintype "passive"))
      (node (ref "U$1") (pin "12") (pinfunction "VCC_12") (pintype "power_in"))
    )
    (net (code "146") (name "USER_CLK") (class "Default")
      (node (ref "U6") (pin "3") (pinfunction "OUT_3") (pintype "output"))
      (node (ref "USR_CLK") (pin "3") (pinfunction "3_3") (pintype "passive"))
    )
    (net (code "147") (name "VCCINT") (class "Default")
      (node (ref "C14") (pin "1") (pinfunction "1_1") (pintype "passive"))
      (node (ref "C15") (pin "1") (pinfunction "1_1") (pintype "passive"))
      (node (ref "C16") (pin "1") (pinfunction "1_1") (pintype "passive"))
      (node (ref "C17") (pin "1") (pinfunction "1_1") (pintype "passive"))
      (node (ref "C32") (pin "1") (pinfunction "1_1") (pintype "passive"))
      (node (ref "C33") (pin "1") (pinfunction "1_1") (pintype "passive"))
      (node (ref "T3") (pin "4") (pinfunction "S_4") (pintype "passive"))
      (node (ref "U1") (pin "122") (pinfunction "P122,VCCINT,VCCINT,VCCINT,_122") (pintype "passive"))
      (node (ref "U1") (pin "22") (pinfunction "P22,VCCINT,VCCINT,VCCINT,_22") (pintype "passive"))
      (node (ref "U1") (pin "52") (pinfunction "P52,VCCINT,VCCINT,VCCINT,_52") (pintype "passive"))
      (node (ref "U1") (pin "94") (pinfunction "P94,VCCINT,VCCINT,VCCINT,_94") (pintype "passive"))
    )
    (net (code "148") (name "VCCIO") (class "Default")
      (node (ref "C10") (pin "1") (pinfunction "1_1") (pintype "passive"))
      (node (ref "C11") (pin "1") (pinfunction "1_1") (pintype "passive"))
      (node (ref "C12") (pin "1") (pinfunction "1_1") (pintype "passive"))
      (node (ref "C13") (pin "1") (pinfunction "1_1") (pintype "passive"))
      (node (ref "C2") (pin "1") (pinfunction "1_1") (pintype "passive"))
      (node (ref "C23") (pin "+") (pinfunction "+_+") (pintype "passive"))
      (node (ref "C27") (pin "1") (pinfunction "1_1") (pintype "passive"))
      (node (ref "C28") (pin "1") (pinfunction "1_1") (pintype "passive"))
      (node (ref "C29") (pin "1") (pinfunction "1_1") (pintype "passive"))
      (node (ref "C3") (pin "1") (pinfunction "1_1") (pintype "passive"))
      (node (ref "C30") (pin "1") (pinfunction "1_1") (pintype "passive"))
      (node (ref "C31") (pin "1") (pinfunction "1_1") (pintype "passive"))
      (node (ref "C4") (pin "1") (pinfunction "1_1") (pintype "passive"))
      (node (ref "C5") (pin "1") (pinfunction "1_1") (pintype "passive"))
      (node (ref "C6") (pin "1") (pinfunction "1_1") (pintype "passive"))
      (node (ref "C7") (pin "1") (pinfunction "1_1") (pintype "passive"))
      (node (ref "C8") (pin "1") (pinfunction "1_1") (pintype "passive"))
      (node (ref "C9") (pin "1") (pinfunction "1_1") (pintype "passive"))
      (node (ref "INIT") (pin "A") (pinfunction "A_A") (pintype "passive"))
      (node (ref "JTAG") (pin "2") (pinfunction "2_2") (pintype "passive"))
      (node (ref "R1") (pin "2") (pinfunction "2_2") (pintype "passive"))
      (node (ref "R10") (pin "2") (pinfunction "2_2") (pintype "passive"))
      (node (ref "R16") (pin "1") (pinfunction "1_1") (pintype "passive"))
      (node (ref "R2") (pin "2") (pinfunction "2_2") (pintype "passive"))
      (node (ref "R3") (pin "1") (pinfunction "1_1") (pintype "passive"))
      (node (ref "T1") (pin "1") (pinfunction "G_1") (pintype "passive"))
      (node (ref "T2") (pin "1") (pinfunction "G_1") (pintype "passive"))
      (node (ref "TP2") (pin "PP") (pinfunction "TP_PP") (pintype "input"))
      (node (ref "U1") (pin "108") (pinfunction "P108,VCCAUX,VCCAUX,VCCAUX,_108") (pintype "passive"))
      (node (ref "U1") (pin "119") (pinfunction "P119,VCCO_0,0,VCCO,_119") (pintype "passive"))
      (node (ref "U1") (pin "133") (pinfunction "P133,VCCAUX,VCCAUX,VCCAUX,_133") (pintype "passive"))
      (node (ref "U1") (pin "136") (pinfunction "P136,VCCO_0,0,VCCO,_136") (pintype "passive"))
      (node (ref "U1") (pin "14") (pinfunction "P14,VCCO_3,3,VCCO,_14") (pintype "passive"))
      (node (ref "U1") (pin "23") (pinfunction "P23,VCCO_3,3,VCCO,_23") (pintype "passive"))
      (node (ref "U1") (pin "36") (pinfunction "P36,VCCAUX,VCCAUX,VCCAUX,_36") (pintype "passive"))
      (node (ref "U1") (pin "40") (pinfunction "P40,VCCO_2,2,VCCO,_40") (pintype "passive"))
      (node (ref "U1") (pin "61") (pinfunction "P61,VCCO_2,2,VCCO,_61") (pintype "passive"))
      (node (ref "U1") (pin "66") (pinfunction "P66,VCCAUX,VCCAUX,VCCAUX,_66") (pintype "passive"))
      (node (ref "U1") (pin "86") (pinfunction "P86,VCCO_1,1,VCCO,_86") (pintype "passive"))
      (node (ref "U1") (pin "95") (pinfunction "P95,VCCO_1,1,VCCO,_95") (pintype "passive"))
      (node (ref "U3") (pin "14") (pinfunction "VOUT2_14") (pintype "bidirectional"))
      (node (ref "U3") (pin "15") (pinfunction "VOUT2_15") (pintype "bidirectional"))
      (node (ref "U6") (pin "4") (pinfunction "VCC_4") (pintype "power_in"))
    )
    (net (code "149") (name "VS0") (class "Default")
      (node (ref "M0|M1|M2|VS2|VS1|VS0") (pin "1") (pinfunction "1_1") (pintype "passive"))
      (node (ref "U1") (pin "45") (pinfunction "P45,IO_L04N_2/VS0,2,DUAL,TRUE_45") (pintype "passive"))
    )
    (net (code "150") (name "VS1") (class "Default")
      (node (ref "M0|M1|M2|VS2|VS1|VS0") (pin "2") (pinfunction "2_2") (pintype "passive"))
      (node (ref "U1") (pin "44") (pinfunction "P44,IO_L03N_2/VS1,2,DUAL,TRUE_44") (pintype "passive"))
    )
    (net (code "151") (name "VS2") (class "Default")
      (node (ref "M0|M1|M2|VS2|VS1|VS0") (pin "3") (pinfunction "3_3") (pintype "passive"))
      (node (ref "U1") (pin "43") (pinfunction "P43,IO_L04P_2/VS2,2,DUAL,TRUE_43") (pintype "passive"))
    )
    (net (code "152") (name "WR") (class "Default")
      (node (ref "LCD") (pin "21") (pinfunction "WR_21") (pintype "bidirectional"))
      (node (ref "U1") (pin "92") (pinfunction "P92,IO_L06N_1/RHCLK5,1,RHCLK,TRUE_92") (pintype "passive"))
    )
    (net (code "153") (name "unconnected-(BATT-+-Pad+@1)") (class "Default")
      (node (ref "BATT") (pin "+@1") (pinfunction "+_+@1") (pintype "passive"))
    )
    (net (code "154") (name "unconnected-(CSI-2A-S-PadP$1)") (class "Default")
      (node (ref "CSI-2") (pin "P$1") (pinfunction "S_P$1") (pintype "passive"))
    )
    (net (code "155") (name "unconnected-(DSIA-S-PadP$1)") (class "Default")
      (node (ref "DSI") (pin "P$1") (pinfunction "S_P$1") (pintype "passive"))
    )
    (net (code "156") (name "unconnected-(DSIH-S-PadP$2)") (class "Default")
      (node (ref "DSI") (pin "P$2") (pinfunction "S_P$2") (pintype "passive"))
    )
    (net (code "157") (name "unconnected-(DSIJ-S-PadP$4)") (class "Default")
      (node (ref "DSI") (pin "P$4") (pinfunction "S_P$4") (pintype "passive"))
    )
    (net (code "158") (name "unconnected-(DSIK-S-PadP$5)") (class "Default")
      (node (ref "DSI") (pin "P$5") (pinfunction "S_P$5") (pintype "passive"))
    )
    (net (code "159") (name "unconnected-(JTAG-Pad12)") (class "Default")
      (node (ref "JTAG") (pin "12") (pinfunction "12_12") (pintype "passive"))
    )
    (net (code "160") (name "unconnected-(JTAG-Pad13)") (class "Default")
      (node (ref "JTAG") (pin "13") (pinfunction "13_13") (pintype "passive"))
    )
    (net (code "161") (name "unconnected-(JTAG-Pad14)") (class "Default")
      (node (ref "JTAG") (pin "14") (pinfunction "14_14") (pintype "passive"))
    )
    (net (code "162") (name "unconnected-(POWER-Pad2)") (class "Default")
      (node (ref "POWER") (pin "2") (pinfunction "2_2") (pintype "passive"))
    )
    (net (code "163") (name "unconnected-(PROG_B-P1-Pad4)") (class "Default")
      (node (ref "PROG_B") (pin "4") (pinfunction "P1_4") (pintype "passive"))
    )
    (net (code "164") (name "unconnected-(PROG_B-S1-Pad2)") (class "Default")
      (node (ref "PROG_B") (pin "2") (pinfunction "S1_2") (pintype "passive"))
    )
    (net (code "165") (name "unconnected-(RESET-P-Pad3)") (class "Default")
      (node (ref "RESET") (pin "3") (pinfunction "P_3") (pintype "passive"))
    )
    (net (code "166") (name "unconnected-(RESET-S-Pad1)") (class "Default")
      (node (ref "RESET") (pin "1") (pinfunction "S_1") (pintype "passive"))
    )
    (net (code "167") (name "unconnected-(U$1-CBUS0-Pad15)") (class "Default")
      (node (ref "U$1") (pin "15") (pinfunction "CBUS0_15") (pintype "bidirectional"))
    )
    (net (code "168") (name "unconnected-(U$1-CBUS3-Pad16)") (class "Default")
      (node (ref "U$1") (pin "16") (pinfunction "CBUS3_16") (pintype "bidirectional"))
    )
    (net (code "169") (name "unconnected-(U$1-~{CTS}-Pad6)") (class "Default")
      (node (ref "U$1") (pin "6") (pinfunction "~{CTS}_6") (pintype "input"))
    )
    (net (code "170") (name "unconnected-(U$1-~{RTS}-Pad2)") (class "Default")
      (node (ref "U$1") (pin "2") (pinfunction "~{RTS}_2") (pintype "output"))
    )
    (net (code "171") (name "unconnected-(U1-P42,IO_L03P_2{slash}RDWR_B,2,DUAL,TRUE-Pad42)") (class "Default")
      (node (ref "U1") (pin "42") (pinfunction "P42,IO_L03P_2/RDWR_B,2,DUAL,TRUE_42") (pintype "passive"))
    )
    (net (code "172") (name "unconnected-(U1-P53,IP_2{slash}VREF_2,2,VREF,-Pad53)") (class "Default")
      (node (ref "U1") (pin "53") (pinfunction "P53,IP_2/VREF_2,2,VREF,_53") (pintype "passive"))
    )
    (net (code "173") (name "unconnected-(U2-SQW{slash}OUT-Pad7)") (class "Default")
      (node (ref "U2") (pin "7") (pinfunction "SQW/OUT_7") (pintype "bidirectional"))
    )
    (net (code "174") (name "unconnected-(U3-MR-Pad5)") (class "Default")
      (node (ref "U3") (pin "5") (pinfunction "MR_5") (pintype "bidirectional"))
    )
    (net (code "175") (name "unconnected-(U3-PG2-Pad18)") (class "Default")
      (node (ref "U3") (pin "18") (pinfunction "PG2_18") (pintype "bidirectional"))
    )
    (net (code "176") (name "unconnected-(U3-RESET-Pad8)") (class "Default")
      (node (ref "U3") (pin "8") (pinfunction "RESET_8") (pintype "bidirectional"))
    )
    (net (code "177") (name "unconnected-(U4-3V3-PadP1_1)") (class "Default")
      (node (ref "U4") (pin "P1_1") (pinfunction "3V3_P1_1") (pintype "bidirectional"))
    )
    (net (code "178") (name "unconnected-(U4-3V3-PadP1_17)") (class "Default")
      (node (ref "U4") (pin "P1_17") (pinfunction "3V3_P1_17") (pintype "bidirectional"))
    )
    (net (code "179") (name "unconnected-(U4-3V3-PadP5_2)") (class "Default")
      (node (ref "U4") (pin "P5_2") (pinfunction "3V3_P5_2") (pintype "bidirectional"))
    )
    (net (code "180") (name "unconnected-(U4-5V-PadP5_1)") (class "Default")
      (node (ref "U4") (pin "P5_1") (pinfunction "5V_P5_1") (pintype "bidirectional"))
    )
    (net (code "181") (name "unconnected-(U6-E{slash}D-Pad1)") (class "Default")
      (node (ref "U6") (pin "1") (pinfunction "E/D_1") (pintype "input"))
    )
    (net (code "182") (name "unconnected-(USB-RS232-Pad4)") (class "Default")
      (node (ref "USB-RS232") (pin "4") (pinfunction "4_4") (pintype "passive"))
    )
  )
)
